# controller.net
KiCad netlist of a schematic drawn in EAGLE
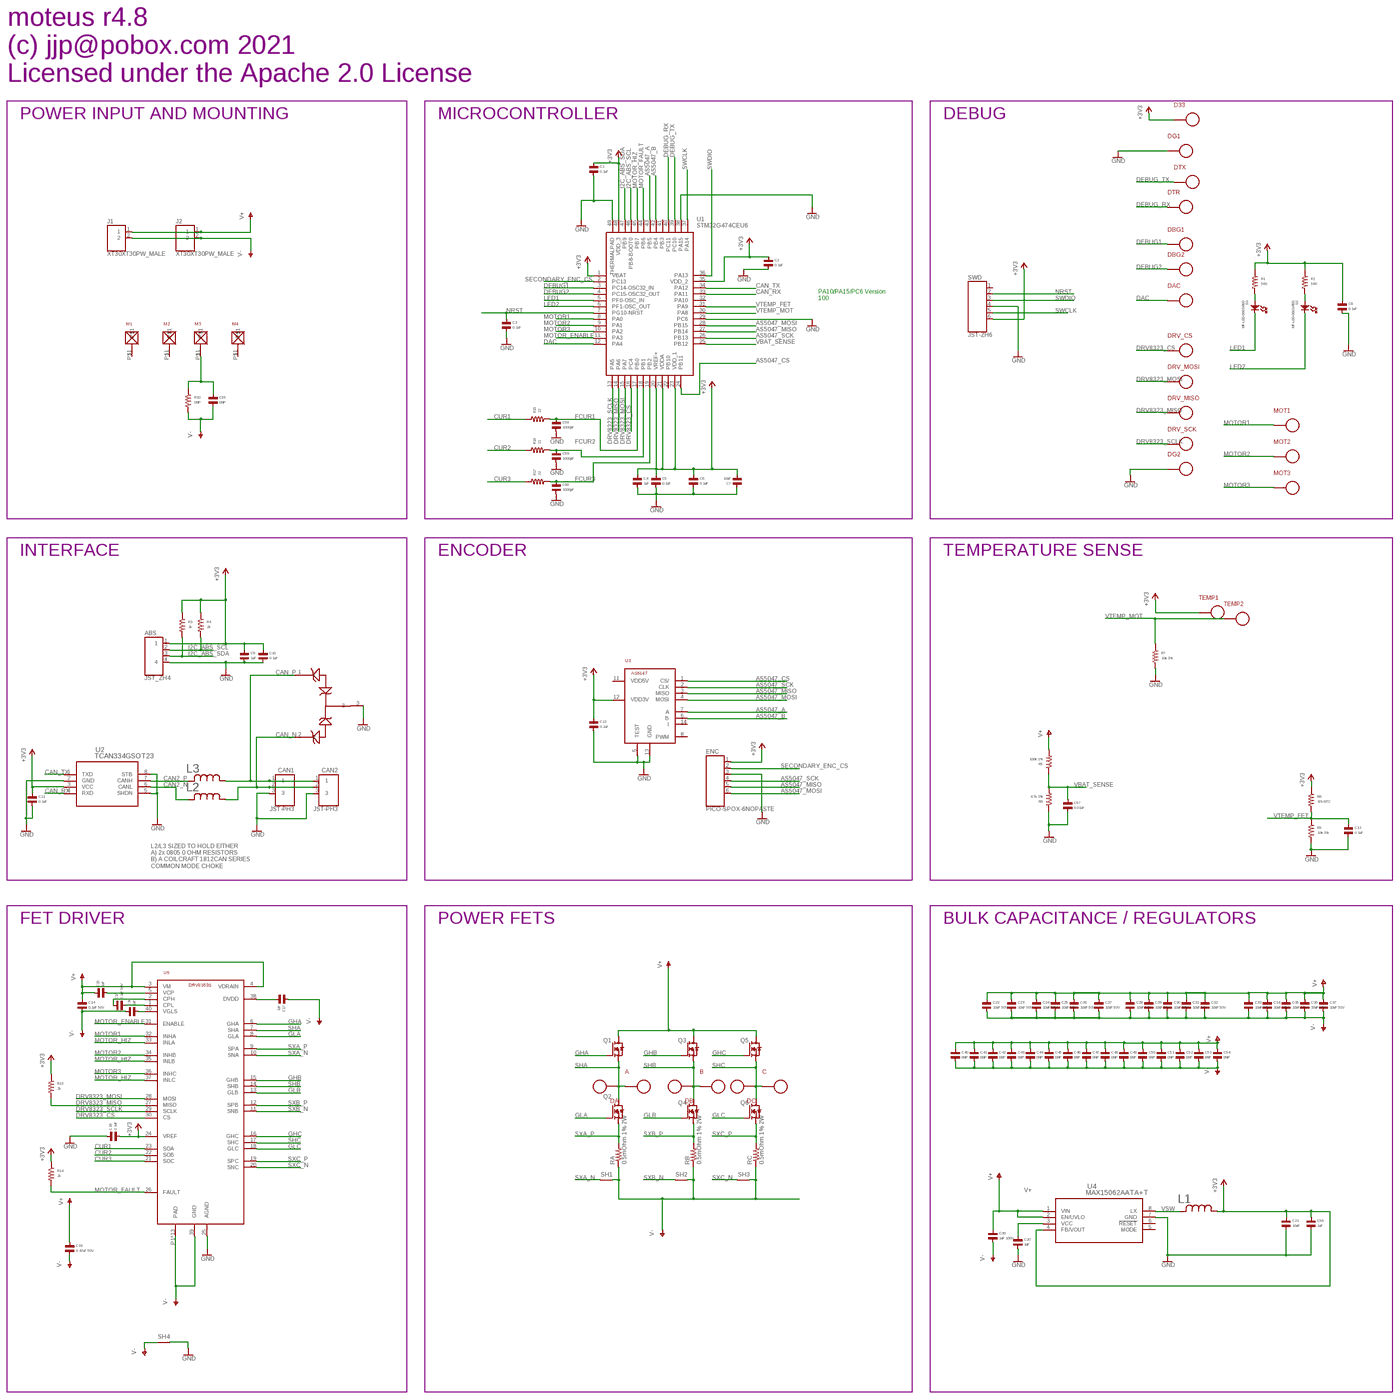
[diagram p0: schematic, sheet 1, overview]
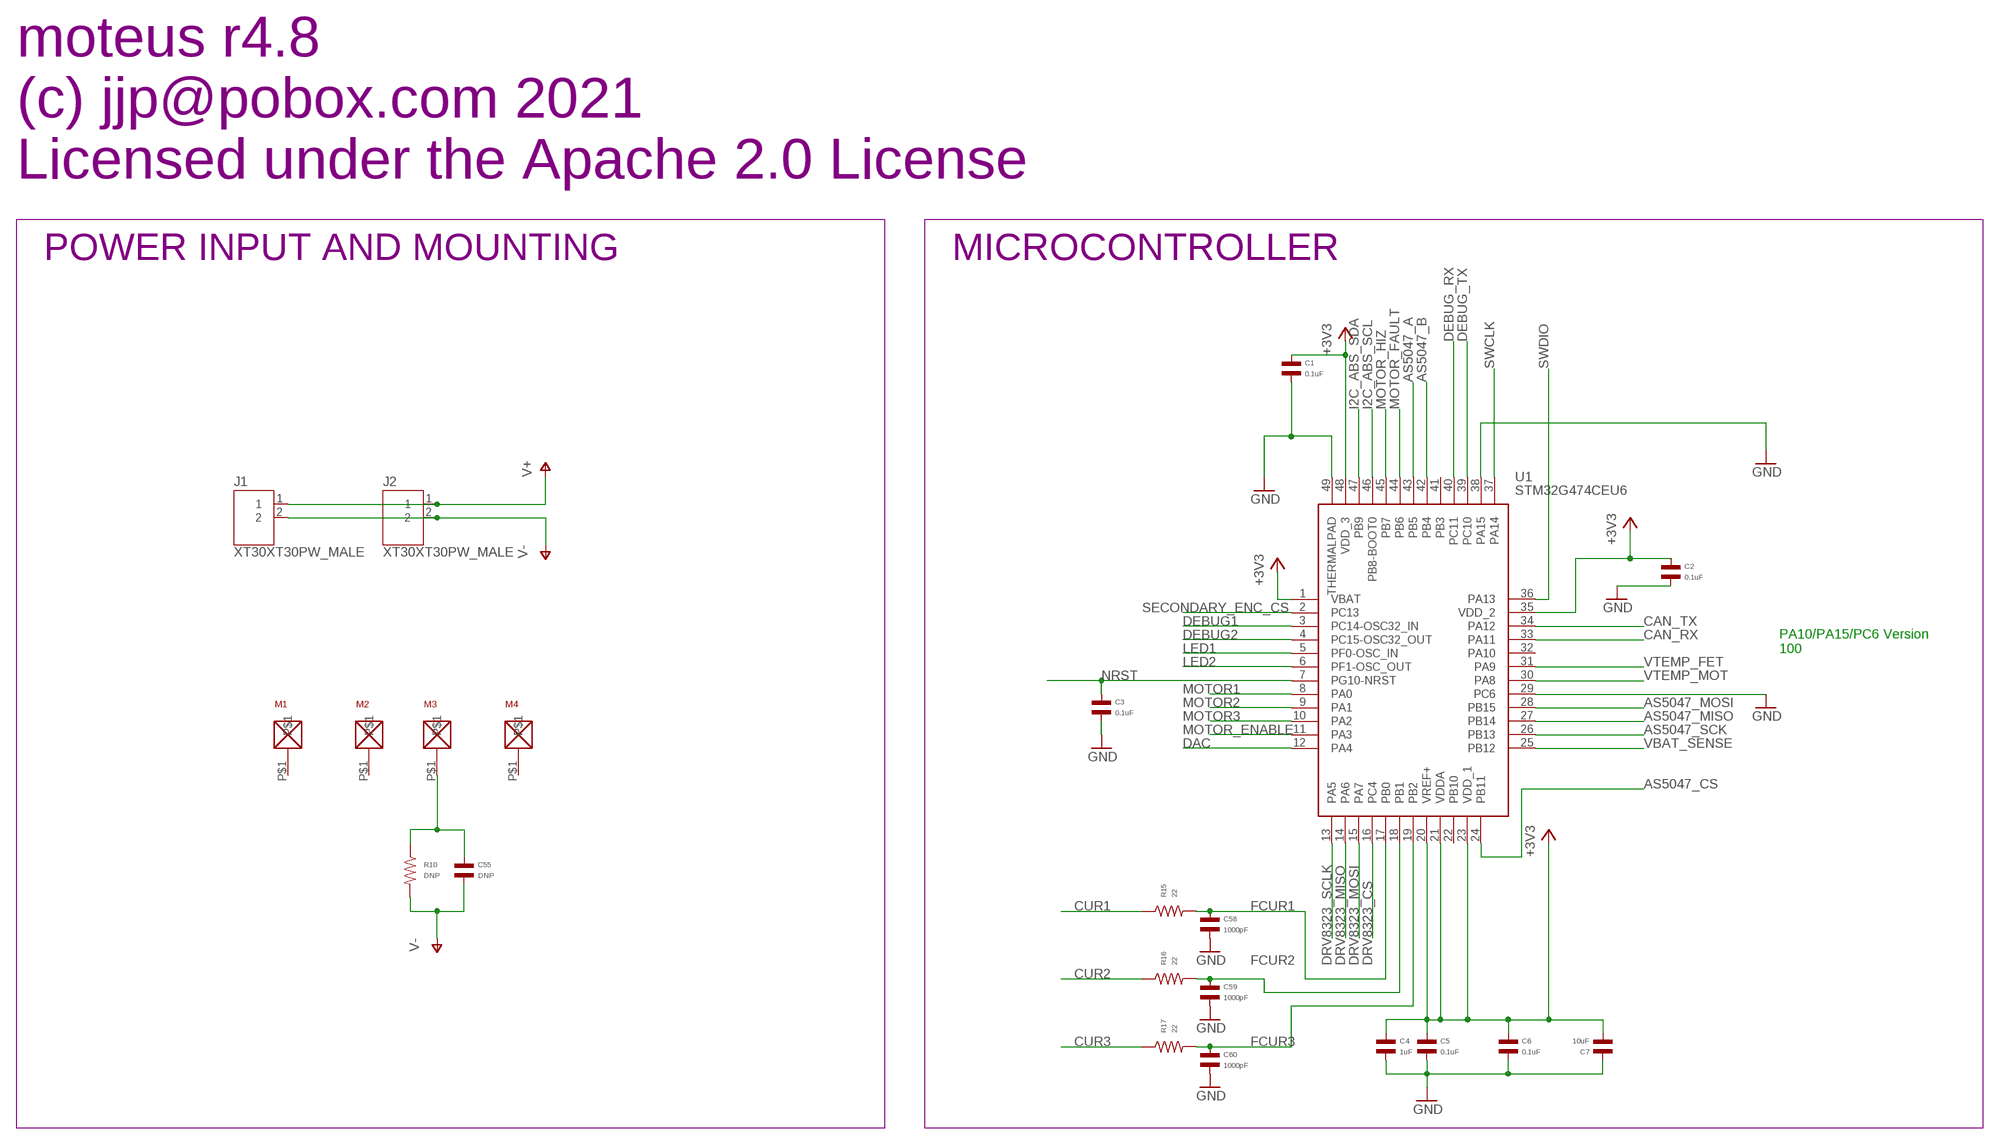
[diagram p1: schematic, sheet 1, part 1 of 4]
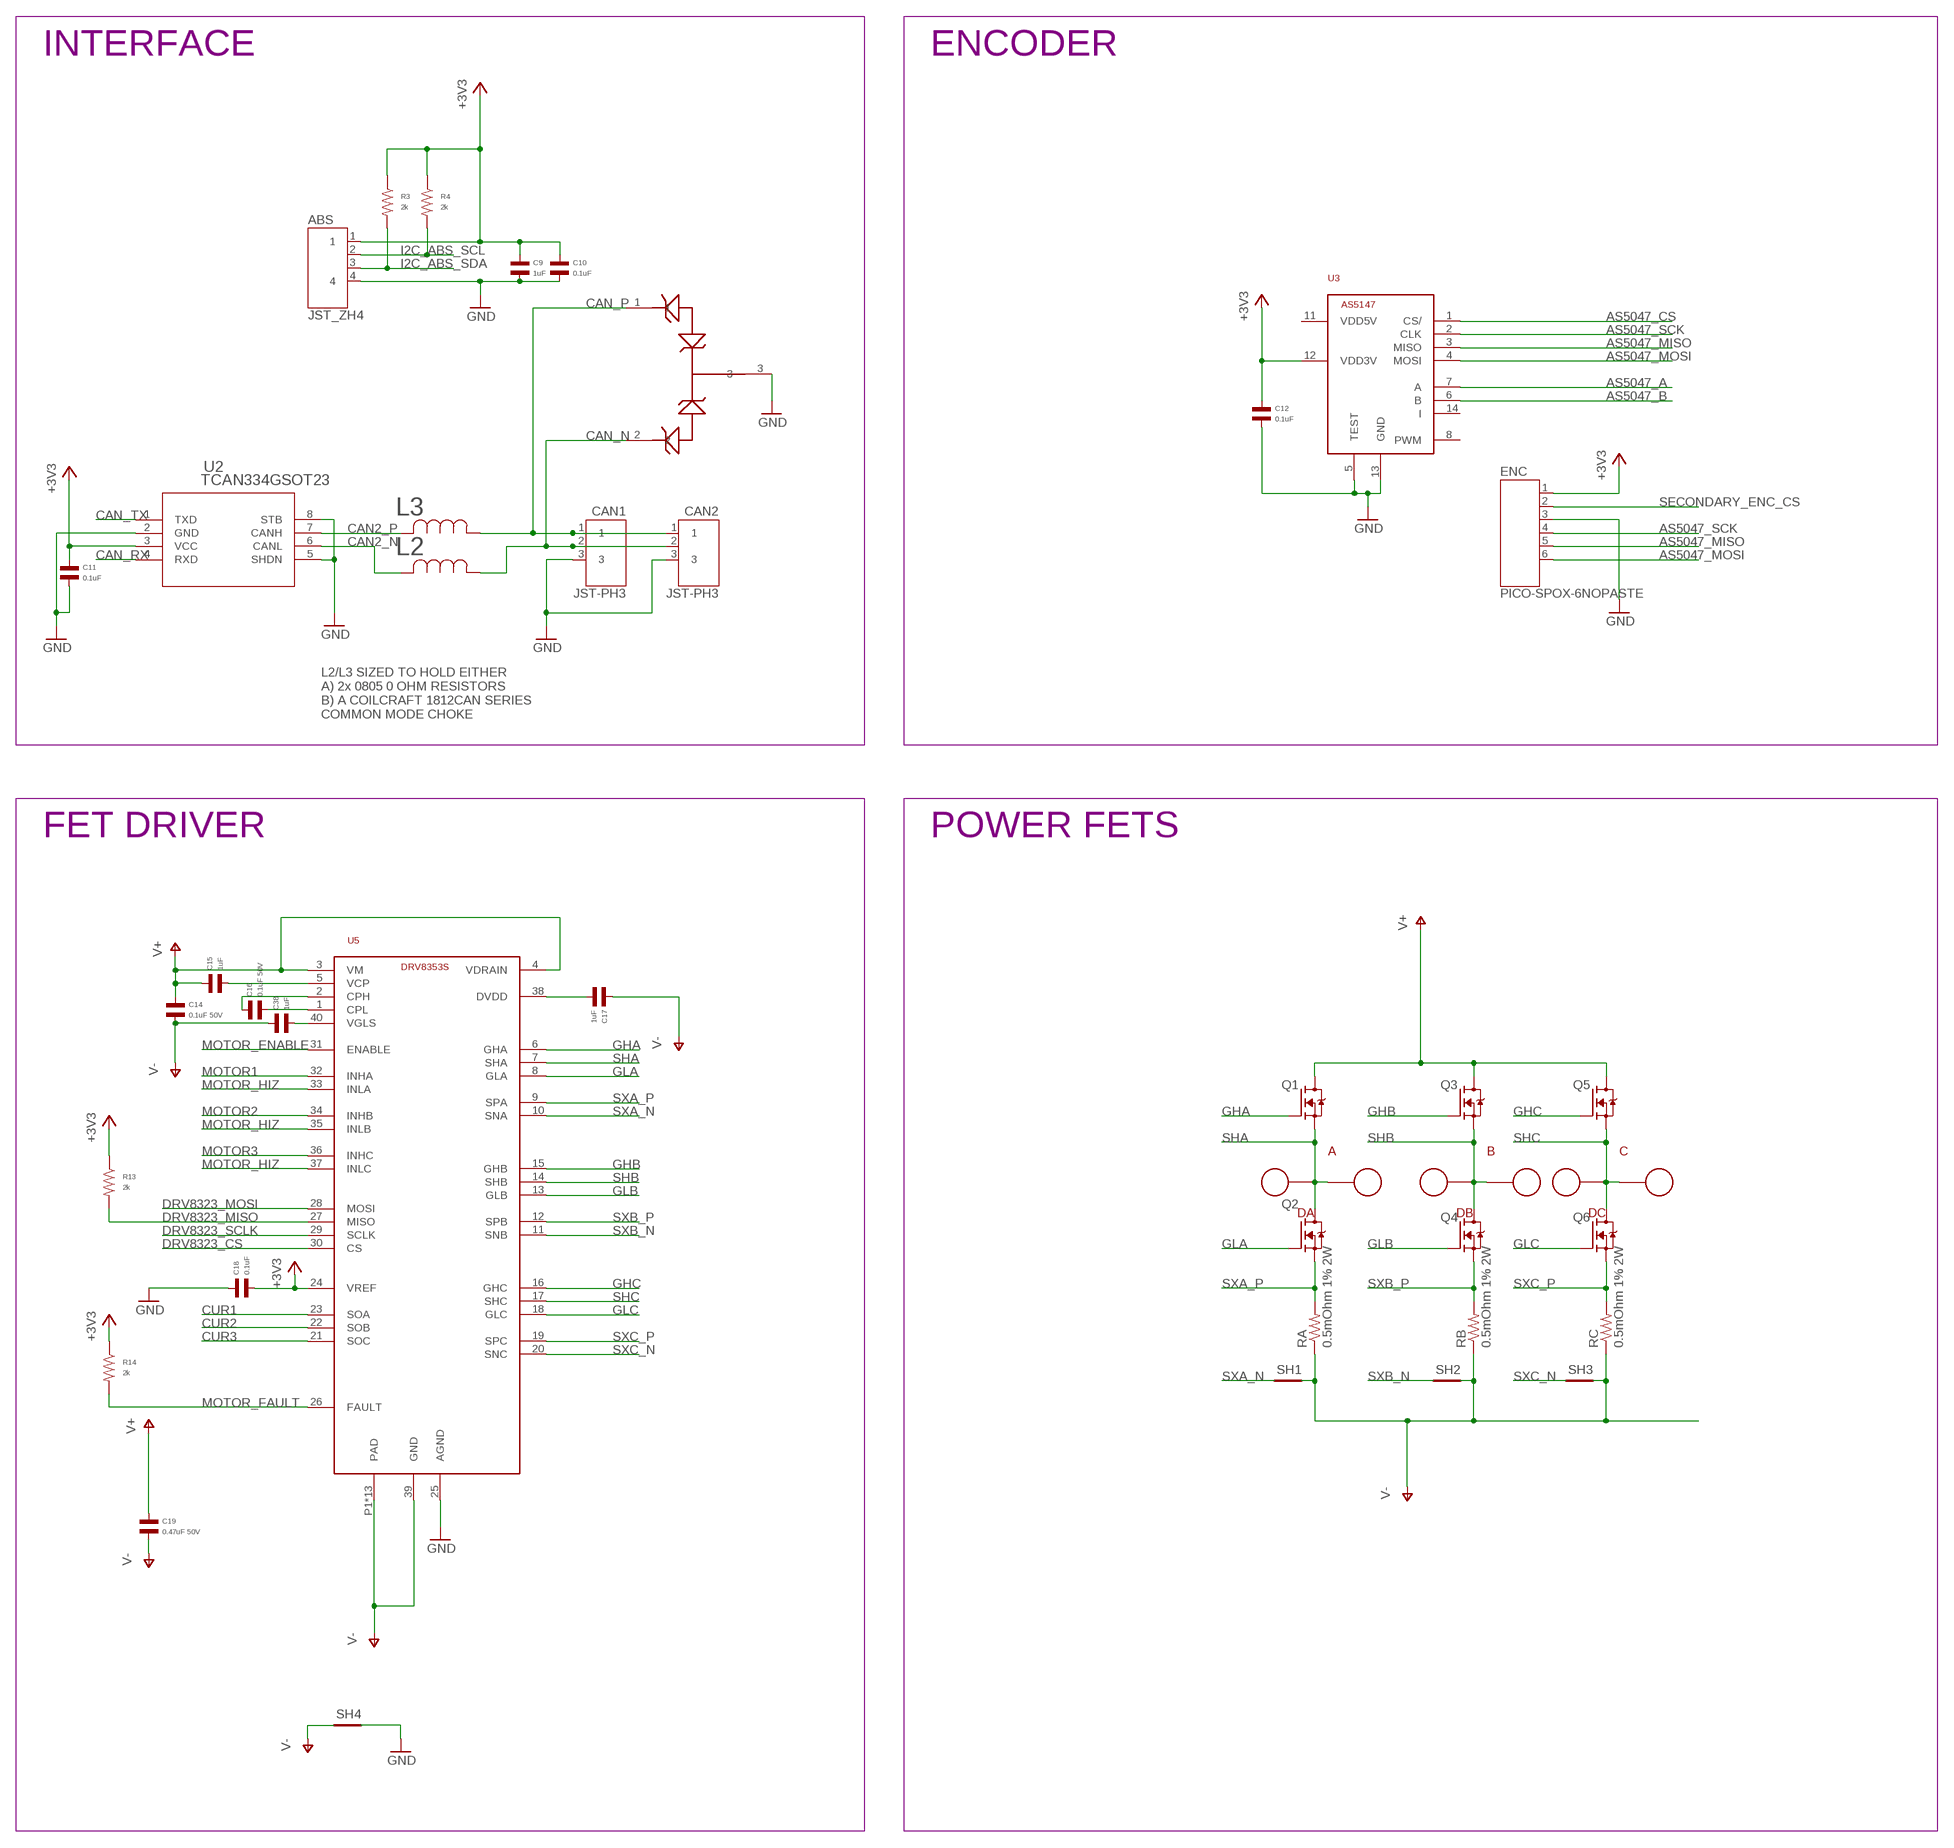
[diagram p2: schematic, sheet 1, part 2 of 4]
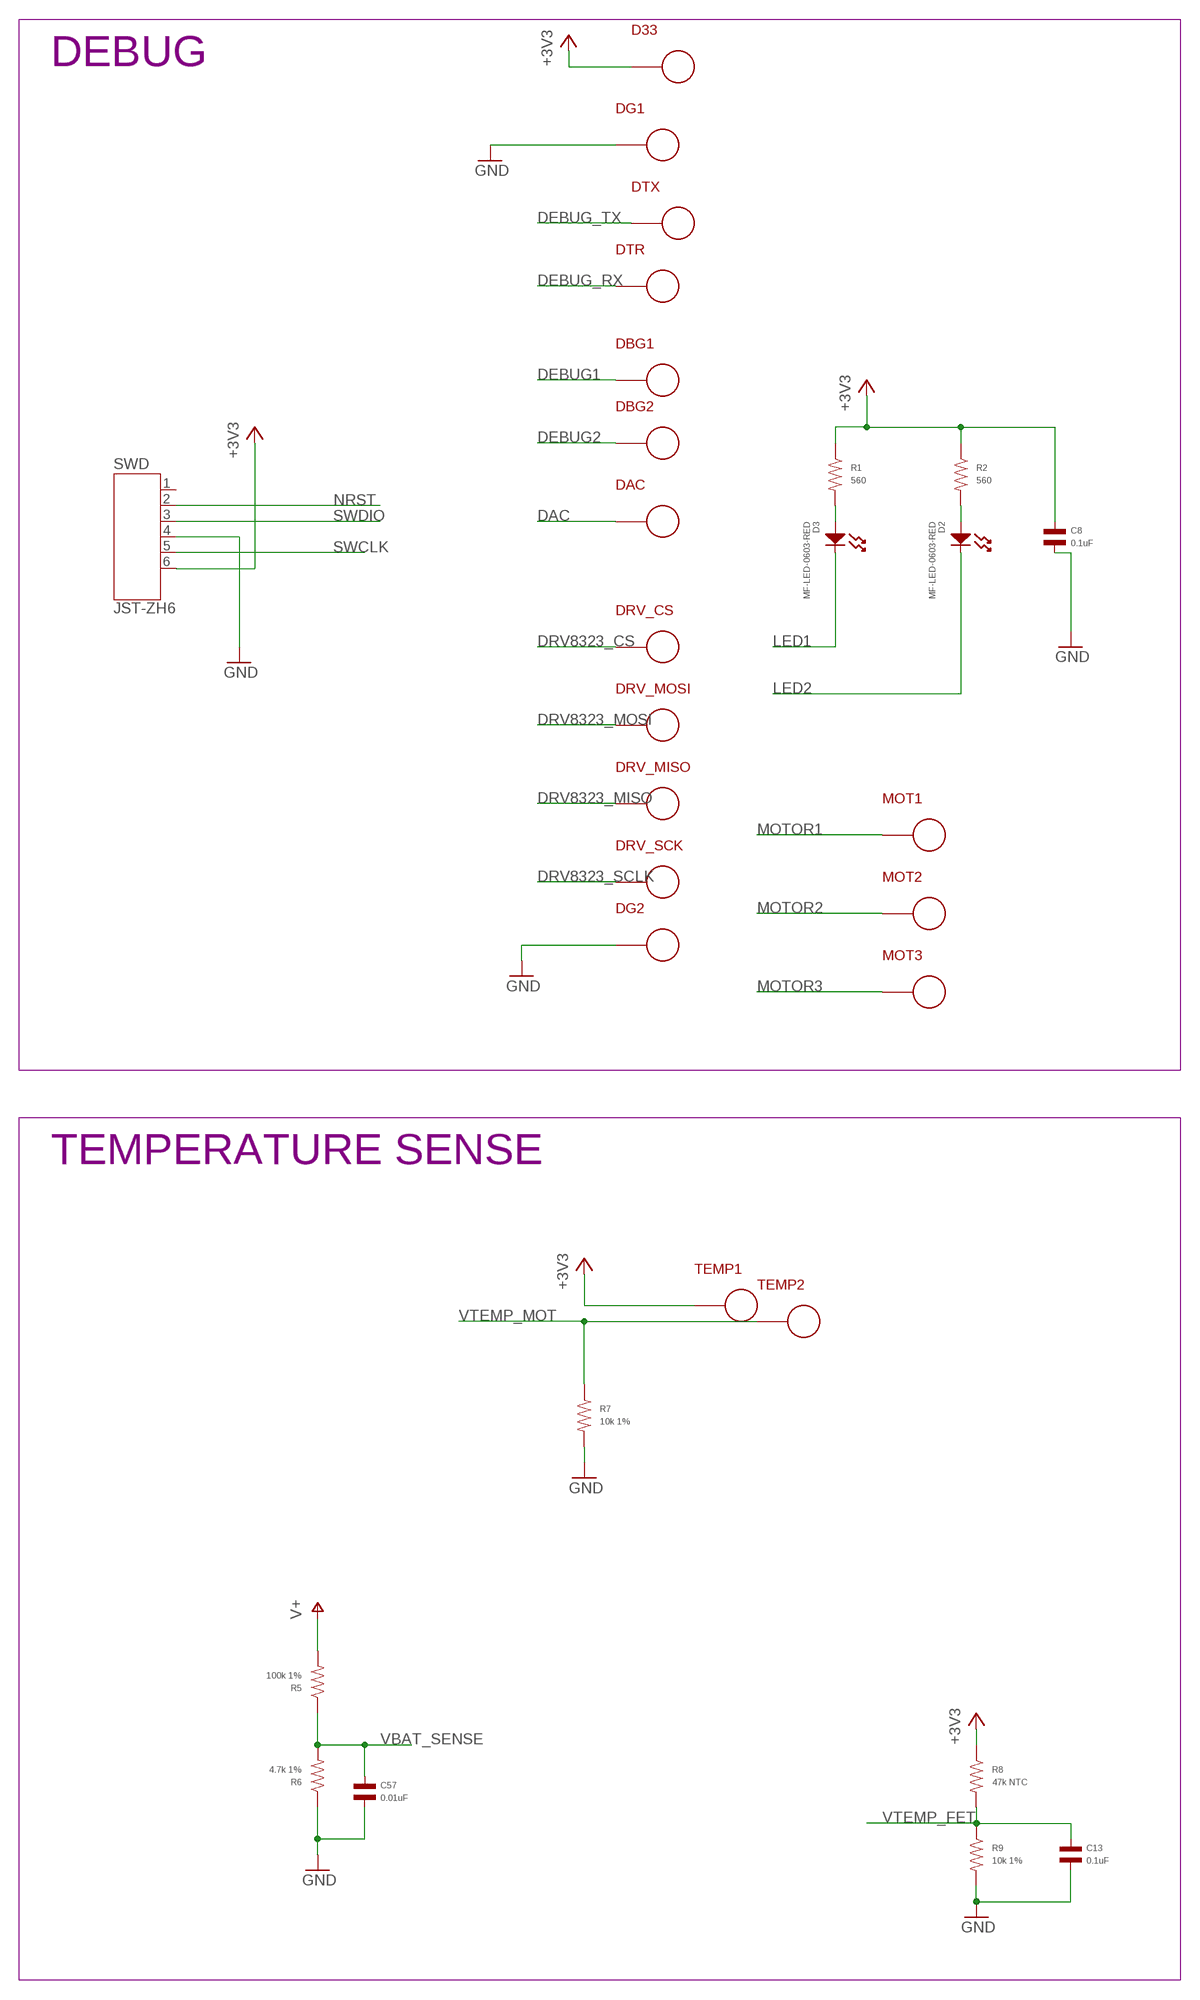
[diagram p3: schematic, sheet 1, part 3 of 4]
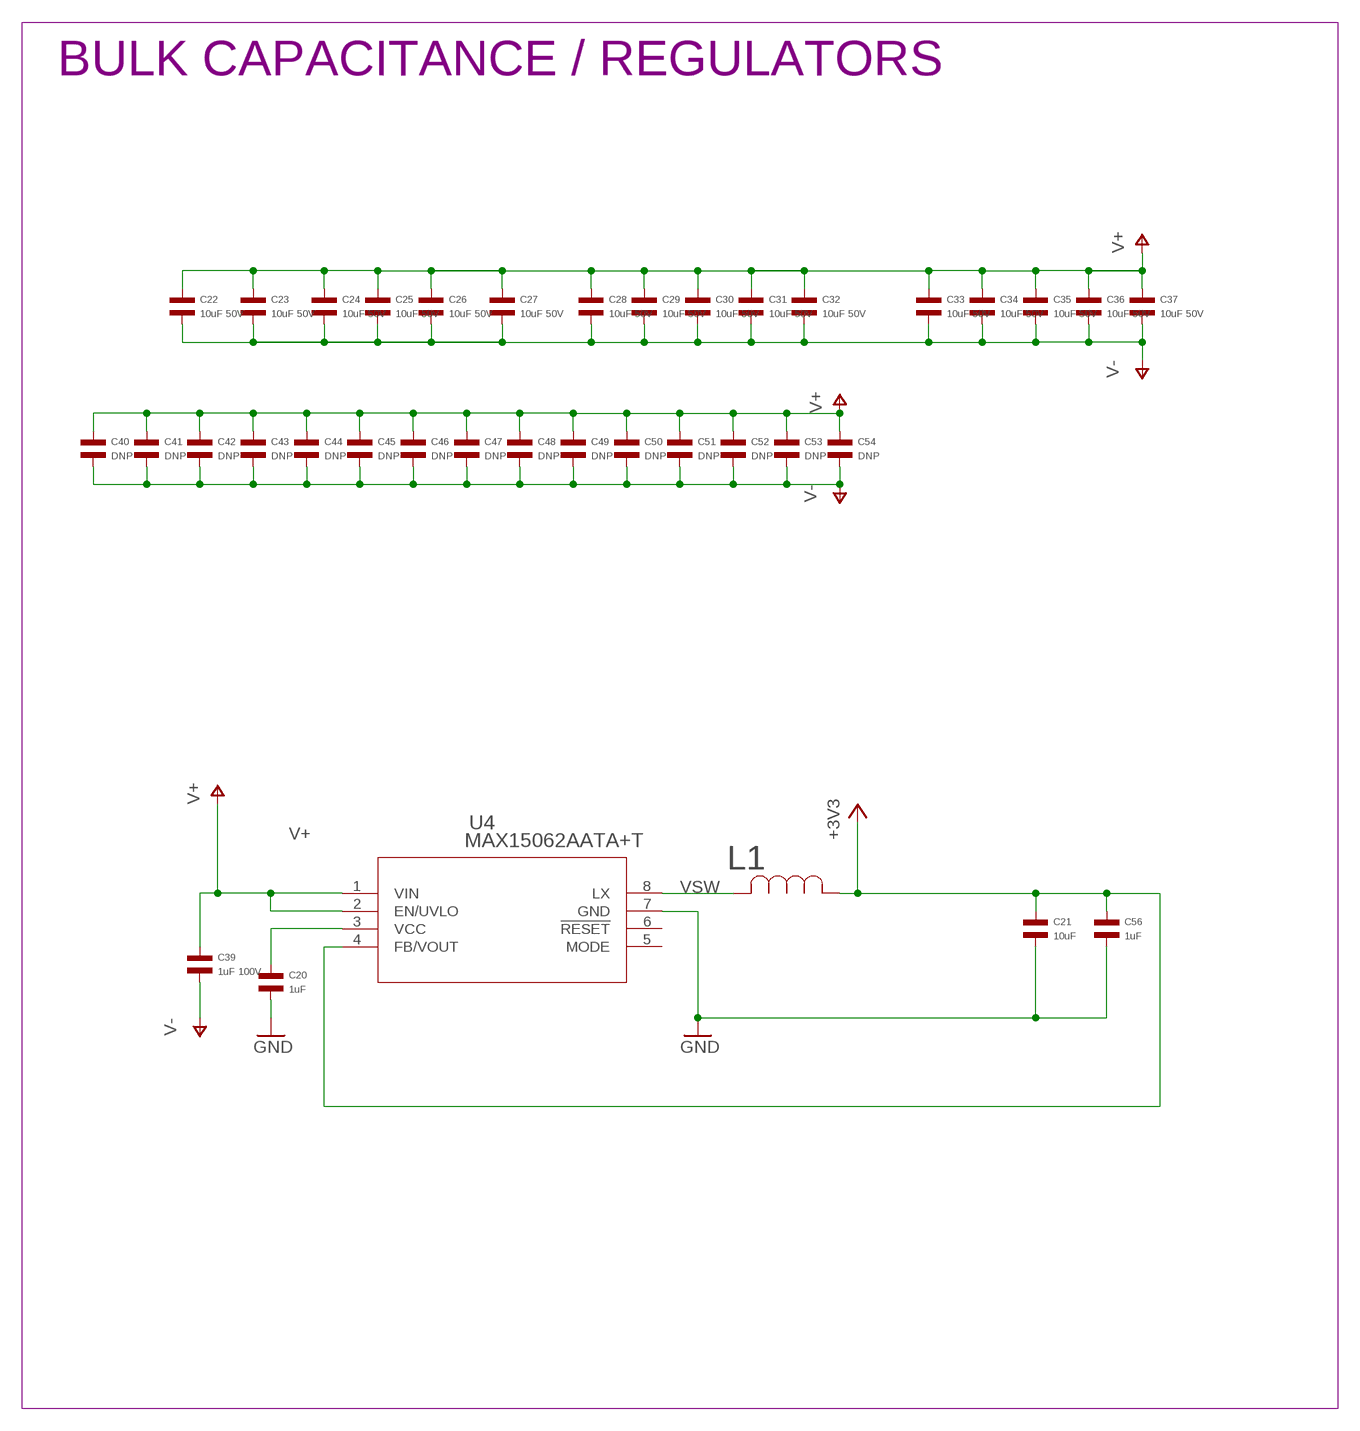
[diagram p4: schematic, sheet 1, part 4 of 4]

(export (version "E")
  (design (tool "Eeschema 10.0.6"))
  (components
    (comp (ref "A")
      (value "PAD16AWG_PAD")
      (footprint "eagle-import:16AWG_PAD")
      (libsource (lib "eagle-import") (part "PAD16AWG_PAD"))
    )
    (comp (ref "ABS")
      (value "JST_ZH4")
      (footprint "eagle-import:JST_S4B-ZR-SM4A-TF(LF)(SN)")
      (fields (field (name "MF") "JST") (field (name "MPN") "S4B-ZR-SM4A-TF(LF)(SN)"))
      (libsource (lib "eagle-import") (part "JST_ZH4"))
    )
    (comp (ref "B")
      (value "PAD16AWG_PAD")
      (footprint "eagle-import:16AWG_PAD")
      (libsource (lib "eagle-import") (part "PAD16AWG_PAD"))
    )
    (comp (ref "C")
      (value "PAD16AWG_PAD")
      (footprint "eagle-import:16AWG_PAD")
      (libsource (lib "eagle-import") (part "PAD16AWG_PAD"))
    )
    (comp (ref "C1")
      (value "0.1uF")
      (footprint "eagle-import:C0402")
      (fields (field (name "HOUSEPART") "YES") (field (name "MPN") "MF-CAP-0402-0.1uF"))
      (libsource (lib "eagle-import") (part "mfpassives_CAPACITOR_NP_0402"))
    )
    (comp (ref "C2")
      (value "0.1uF")
      (footprint "eagle-import:C0402")
      (fields (field (name "HOUSEPART") "YES") (field (name "MPN") "MF-CAP-0402-0.1uF"))
      (libsource (lib "eagle-import") (part "mfpassives_CAPACITOR_NP_0402"))
    )
    (comp (ref "C3")
      (value "0.1uF")
      (footprint "eagle-import:C0402")
      (fields (field (name "HOUSEPART") "YES") (field (name "MPN") "MF-CAP-0402-0.1uF"))
      (libsource (lib "eagle-import") (part "mfpassives_CAPACITOR_NP_0402"))
    )
    (comp (ref "C4")
      (value "1uF")
      (footprint "eagle-import:C0402")
      (fields (field (name "HOUSEPART") "YES") (field (name "MPN") "MF-CAP-0402-1uF"))
      (libsource (lib "eagle-import") (part "mfpassives_CAPACITOR_NP_0402"))
    )
    (comp (ref "C5")
      (value "0.1uF")
      (footprint "eagle-import:C0402")
      (fields (field (name "HOUSEPART") "YES") (field (name "MPN") "MF-CAP-0402-0.1uF"))
      (libsource (lib "eagle-import") (part "mfpassives_CAPACITOR_NP_0402"))
    )
    (comp (ref "C6")
      (value "0.1uF")
      (footprint "eagle-import:C0402")
      (fields (field (name "HOUSEPART") "YES") (field (name "MPN") "MF-CAP-0402-0.1uF"))
      (libsource (lib "eagle-import") (part "mfpassives_CAPACITOR_NP_0402"))
    )
    (comp (ref "C7")
      (value "10uF")
      (footprint "eagle-import:C1206")
      (fields (field (name "HOUSEPART") "YES") (field (name "MPN") "MF-CAP-1206-10uF"))
      (libsource (lib "eagle-import") (part "mfpassives_CAPACITOR_NP_1206"))
    )
    (comp (ref "C8")
      (value "0.1uF")
      (footprint "eagle-import:C0402")
      (fields (field (name "HOUSEPART") "YES") (field (name "MPN") "MF-CAP-0402-0.1uF"))
      (libsource (lib "eagle-import") (part "mfpassives_CAPACITOR_NP_0402"))
    )
    (comp (ref "C9")
      (value "1uF")
      (footprint "eagle-import:C0402")
      (fields (field (name "HOUSEPART") "YES") (field (name "MPN") "MF-CAP-0402-1uF"))
      (libsource (lib "eagle-import") (part "mfpassives_CAPACITOR_NP_0402"))
    )
    (comp (ref "C10")
      (value "0.1uF")
      (footprint "eagle-import:C0402")
      (fields (field (name "HOUSEPART") "YES") (field (name "MPN") "MF-CAP-0402-0.1uF"))
      (libsource (lib "eagle-import") (part "mfpassives_CAPACITOR_NP_0402"))
    )
    (comp (ref "C11")
      (value "0.1uF")
      (footprint "eagle-import:C0402")
      (fields (field (name "HOUSEPART") "YES") (field (name "MPN") "MF-CAP-0402-0.1uF"))
      (libsource (lib "eagle-import") (part "mfpassives_CAPACITOR_NP_0402"))
    )
    (comp (ref "C12")
      (value "0.1uF")
      (footprint "eagle-import:C0402")
      (fields (field (name "HOUSEPART") "YES") (field (name "MPN") "MF-CAP-0402-0.1uF"))
      (libsource (lib "eagle-import") (part "mfpassives_CAPACITOR_NP_0402"))
    )
    (comp (ref "C13")
      (value "0.1uF")
      (footprint "eagle-import:C0402")
      (fields (field (name "HOUSEPART") "YES") (field (name "MPN") "MF-CAP-0402-0.1uF"))
      (libsource (lib "eagle-import") (part "mfpassives_CAPACITOR_NP_0402"))
    )
    (comp (ref "C14")
      (value "0.1uF 50V")
      (footprint "eagle-import:C0402")
      (fields (field (name "MF") "TDK") (field (name "MPN") "CGA2B3X7R1H104K050BB"))
      (libsource (lib "eagle-import") (part "mfpassives_CAPACITOR_NP_0402"))
    )
    (comp (ref "C15")
      (value "1uF")
      (footprint "eagle-import:C0402")
      (fields (field (name "HOUSEPART") "YES") (field (name "MPN") "MF-CAP-0402-1uF"))
      (libsource (lib "eagle-import") (part "mfpassives_CAPACITOR_NP_0402"))
    )
    (comp (ref "C16")
      (value "0.1uF 50V")
      (footprint "eagle-import:C0402")
      (fields (field (name "MF") "TDK") (field (name "MPN") "CGA2B3X7R1H104K050BB"))
      (libsource (lib "eagle-import") (part "mfpassives_CAPACITOR_NP_0402"))
    )
    (comp (ref "C17")
      (value "1uF")
      (footprint "eagle-import:C0402")
      (fields (field (name "HOUSEPART") "YES") (field (name "MPN") "MF-CAP-0402-1uF"))
      (libsource (lib "eagle-import") (part "mfpassives_CAPACITOR_NP_0402"))
    )
    (comp (ref "C18")
      (value "0.1uF")
      (footprint "eagle-import:C0402")
      (fields (field (name "HOUSEPART") "YES") (field (name "MPN") "MF-CAP-0402-0.1uF"))
      (libsource (lib "eagle-import") (part "mfpassives_CAPACITOR_NP_0402"))
    )
    (comp (ref "C19")
      (value "0.47uF 50V")
      (footprint "eagle-import:C0402")
      (fields (field (name "MF") "Murata") (field (name "MPN") "GRM155R61H474KE11D"))
      (libsource (lib "eagle-import") (part "mfpassives_CAPACITOR_NP_0402"))
    )
    (comp (ref "C20")
      (value "1uF")
      (footprint "eagle-import:C0603")
      (fields (field (name "HOUSEPART") "1") (field (name "MPN") "MF-CAP-0603-1uF"))
      (libsource (lib "eagle-import") (part "mfpassives_CAPACITOR_NP_0603"))
    )
    (comp (ref "C21")
      (value "10uF")
      (footprint "eagle-import:C1206")
      (fields (field (name "HOUSEPART") "1") (field (name "MPN") "MF-CAP-1206-10uF"))
      (libsource (lib "eagle-import") (part "mfpassives_CAPACITOR_NP_1206"))
    )
    (comp (ref "C22")
      (value "10uF 50V")
      (footprint "eagle-import:C1206")
      (fields (field (name "MF") "TDK") (field (name "MPN") "C3216X7R1H106K160AE"))
      (libsource (lib "eagle-import") (part "mfpassives_CAPACITOR_NP_1206"))
    )
    (comp (ref "C23")
      (value "10uF 50V")
      (footprint "eagle-import:C1206")
      (fields (field (name "MF") "TDK") (field (name "MPN") "C3216X7R1H106K160AE"))
      (libsource (lib "eagle-import") (part "mfpassives_CAPACITOR_NP_1206"))
    )
    (comp (ref "C24")
      (value "10uF 50V")
      (footprint "eagle-import:C1206")
      (fields (field (name "MF") "TDK") (field (name "MPN") "C3216X7R1H106K160AE"))
      (libsource (lib "eagle-import") (part "mfpassives_CAPACITOR_NP_1206"))
    )
    (comp (ref "C25")
      (value "10uF 50V")
      (footprint "eagle-import:C1206")
      (fields (field (name "MF") "TDK") (field (name "MPN") "C3216X7R1H106K160AE"))
      (libsource (lib "eagle-import") (part "mfpassives_CAPACITOR_NP_1206"))
    )
    (comp (ref "C26")
      (value "10uF 50V")
      (footprint "eagle-import:C1206")
      (fields (field (name "MF") "TDK") (field (name "MPN") "C3216X7R1H106K160AE"))
      (libsource (lib "eagle-import") (part "mfpassives_CAPACITOR_NP_1206"))
    )
    (comp (ref "C27")
      (value "10uF 50V")
      (footprint "eagle-import:C1206")
      (fields (field (name "MF") "TDK") (field (name "MPN") "C3216X7R1H106K160AE"))
      (libsource (lib "eagle-import") (part "mfpassives_CAPACITOR_NP_1206"))
    )
    (comp (ref "C28")
      (value "10uF 50V")
      (footprint "eagle-import:C1206")
      (fields (field (name "MF") "TDK") (field (name "MPN") "C3216X7R1H106K160AE"))
      (libsource (lib "eagle-import") (part "mfpassives_CAPACITOR_NP_1206"))
    )
    (comp (ref "C29")
      (value "10uF 50V")
      (footprint "eagle-import:C1206")
      (fields (field (name "MF") "TDK") (field (name "MPN") "C3216X7R1H106K160AE"))
      (libsource (lib "eagle-import") (part "mfpassives_CAPACITOR_NP_1206"))
    )
    (comp (ref "C30")
      (value "10uF 50V")
      (footprint "eagle-import:C1206")
      (fields (field (name "MF") "TDK") (field (name "MPN") "C3216X7R1H106K160AE"))
      (libsource (lib "eagle-import") (part "mfpassives_CAPACITOR_NP_1206"))
    )
    (comp (ref "C31")
      (value "10uF 50V")
      (footprint "eagle-import:C1206")
      (fields (field (name "MF") "TDK") (field (name "MPN") "C3216X7R1H106K160AE"))
      (libsource (lib "eagle-import") (part "mfpassives_CAPACITOR_NP_1206"))
    )
    (comp (ref "C32")
      (value "10uF 50V")
      (footprint "eagle-import:C1206")
      (fields (field (name "MF") "TDK") (field (name "MPN") "C3216X7R1H106K160AE"))
      (libsource (lib "eagle-import") (part "mfpassives_CAPACITOR_NP_1206"))
    )
    (comp (ref "C33")
      (value "10uF 50V")
      (footprint "eagle-import:C1206")
      (fields (field (name "MF") "TDK") (field (name "MPN") "C3216X7R1H106K160AE"))
      (libsource (lib "eagle-import") (part "mfpassives_CAPACITOR_NP_1206"))
    )
    (comp (ref "C34")
      (value "10uF 50V")
      (footprint "eagle-import:C1206")
      (fields (field (name "MF") "TDK") (field (name "MPN") "C3216X7R1H106K160AE"))
      (libsource (lib "eagle-import") (part "mfpassives_CAPACITOR_NP_1206"))
    )
    (comp (ref "C35")
      (value "10uF 50V")
      (footprint "eagle-import:C1206_NOBORDER")
      (fields (field (name "MF") "TDK") (field (name "MPN") "C3216X7R1H106K160AE"))
      (libsource (lib "eagle-import") (part "CAPACITOR_NP_1206_NOBORDER"))
    )
    (comp (ref "C36")
      (value "10uF 50V")
      (footprint "eagle-import:C1206")
      (fields (field (name "MF") "TDK") (field (name "MPN") "C3216X7R1H106K160AE"))
      (libsource (lib "eagle-import") (part "mfpassives_CAPACITOR_NP_1206"))
    )
    (comp (ref "C37")
      (value "10uF 50V")
      (footprint "eagle-import:C1206")
      (fields (field (name "MF") "TDK") (field (name "MPN") "C3216X7R1H106K160AE"))
      (libsource (lib "eagle-import") (part "mfpassives_CAPACITOR_NP_1206"))
    )
    (comp (ref "C38")
      (value "1uF")
      (footprint "eagle-import:C0402")
      (fields (field (name "HOUSEPART") "YES") (field (name "MPN") "MF-CAP-0402-1uF"))
      (libsource (lib "eagle-import") (part "mfpassives_CAPACITOR_NP_0402"))
    )
    (comp (ref "C39")
      (value "1uF 100V")
      (footprint "eagle-import:C0805")
      (fields (field (name "MF") "MURATA") (field (name "MPN") "GCM21BC72A105KE36L"))
      (libsource (lib "eagle-import") (part "mfpassives_CAPACITOR_NP_0805"))
    )
    (comp (ref "C40")
      (value "DNP")
      (footprint "eagle-import:C1206_NOCREAM")
      (libsource (lib "eagle-import") (part "CAPACITOR_NP_1206_NOCREAM"))
    )
    (comp (ref "C41")
      (value "DNP")
      (footprint "eagle-import:C1206_NOCREAM")
      (libsource (lib "eagle-import") (part "CAPACITOR_NP_1206_NOCREAM"))
    )
    (comp (ref "C42")
      (value "DNP")
      (footprint "eagle-import:C1206_NOCREAM")
      (libsource (lib "eagle-import") (part "CAPACITOR_NP_1206_NOCREAM"))
    )
    (comp (ref "C43")
      (value "DNP")
      (footprint "eagle-import:C1206_NOCREAM")
      (libsource (lib "eagle-import") (part "CAPACITOR_NP_1206_NOCREAM"))
    )
    (comp (ref "C44")
      (value "DNP")
      (footprint "eagle-import:C1206_NOCREAM")
      (libsource (lib "eagle-import") (part "CAPACITOR_NP_1206_NOCREAM"))
    )
    (comp (ref "C45")
      (value "DNP")
      (footprint "eagle-import:C1206_NOCREAM")
      (libsource (lib "eagle-import") (part "CAPACITOR_NP_1206_NOCREAM"))
    )
    (comp (ref "C46")
      (value "DNP")
      (footprint "eagle-import:C1206_NOCREAM")
      (libsource (lib "eagle-import") (part "CAPACITOR_NP_1206_NOCREAM"))
    )
    (comp (ref "C47")
      (value "DNP")
      (footprint "eagle-import:C1206_NOCREAM")
      (libsource (lib "eagle-import") (part "CAPACITOR_NP_1206_NOCREAM"))
    )
    (comp (ref "C48")
      (value "DNP")
      (footprint "eagle-import:C1206_NOCREAM")
      (libsource (lib "eagle-import") (part "CAPACITOR_NP_1206_NOCREAM"))
    )
    (comp (ref "C49")
      (value "DNP")
      (footprint "eagle-import:C1206_NOCREAM")
      (libsource (lib "eagle-import") (part "CAPACITOR_NP_1206_NOCREAM"))
    )
    (comp (ref "C50")
      (value "DNP")
      (footprint "eagle-import:C1206_NOCREAM")
      (libsource (lib "eagle-import") (part "CAPACITOR_NP_1206_NOCREAM"))
    )
    (comp (ref "C51")
      (value "DNP")
      (footprint "eagle-import:C1206_NOCREAM")
      (libsource (lib "eagle-import") (part "CAPACITOR_NP_1206_NOCREAM"))
    )
    (comp (ref "C52")
      (value "DNP")
      (footprint "eagle-import:C1206_NOCREAM")
      (libsource (lib "eagle-import") (part "CAPACITOR_NP_1206_NOCREAM"))
    )
    (comp (ref "C53")
      (value "DNP")
      (footprint "eagle-import:C1206_NOCREAM")
      (libsource (lib "eagle-import") (part "CAPACITOR_NP_1206_NOCREAM"))
    )
    (comp (ref "C54")
      (value "DNP")
      (footprint "eagle-import:C1206_NOCREAM")
      (libsource (lib "eagle-import") (part "CAPACITOR_NP_1206_NOCREAM"))
    )
    (comp (ref "C55")
      (value "DNP")
      (footprint "eagle-import:C0402")
      (fields (field (name "POPULATE") "0"))
      (libsource (lib "eagle-import") (part "mfpassives_CAPACITOR_NP_0402"))
    )
    (comp (ref "C56")
      (value "1uF")
      (footprint "eagle-import:C0402")
      (fields (field (name "HOUSEPART") "YES") (field (name "MPN") "MF-CAP-0402-1uF"))
      (libsource (lib "eagle-import") (part "mfpassives_CAPACITOR_NP_0402"))
    )
    (comp (ref "C57")
      (value "0.01uF")
      (footprint "eagle-import:C0402")
      (fields (field (name "HOUSEPART") "YES") (field (name "MPN") "MF-CAP-0402-0.01uF"))
      (libsource (lib "eagle-import") (part "mfpassives_CAPACITOR_NP_0402"))
    )
    (comp (ref "C58")
      (value "1000pF")
      (footprint "eagle-import:C0402")
      (fields (field (name "HOUSEPART") "1") (field (name "MPN") "MF-CAP-0402-1nF"))
      (libsource (lib "eagle-import") (part "mfpassives_CAPACITOR_NP_0402"))
    )
    (comp (ref "C59")
      (value "1000pF")
      (footprint "eagle-import:C0402")
      (fields (field (name "HOUSEPART") "1") (field (name "MPN") "MF-CAP-0402-1nF"))
      (libsource (lib "eagle-import") (part "mfpassives_CAPACITOR_NP_0402"))
    )
    (comp (ref "C60")
      (value "1000pF")
      (footprint "eagle-import:C0402")
      (fields (field (name "HOUSEPART") "1") (field (name "MPN") "MF-CAP-0402-1nF"))
      (libsource (lib "eagle-import") (part "mfpassives_CAPACITOR_NP_0402"))
    )
    (comp (ref "CAN1")
      (value "JST-PH3")
      (footprint "eagle-import:JST_S3B-PH-SM4-TB(LF)(SN)")
      (fields (field (name "MF") "JST") (field (name "MPN") "S3B-PH-SM4-TB(LF)(SN)"))
      (libsource (lib "eagle-import") (part "JST-PH3"))
    )
    (comp (ref "CAN2")
      (value "JST-PH3")
      (footprint "eagle-import:JST_S3B-PH-SM4-TB(LF)(SN)")
      (fields (field (name "MF") "JST") (field (name "MPN") "S3B-PH-SM4-TB(LF)(SN)"))
      (libsource (lib "eagle-import") (part "JST-PH3"))
    )
    (comp (ref "D2")
      (value "MF-LED-0603-RED")
      (footprint "eagle-import:LED0603")
      (fields (field (name "HOUSEPART") "YES") (field (name "MPN") "MF-LED-0603-GREEN"))
      (libsource (lib "eagle-import") (part "LED_SINGLE-0603-RED"))
    )
    (comp (ref "D3")
      (value "MF-LED-0603-RED")
      (footprint "eagle-import:LED0603")
      (fields (field (name "HOUSEPART") "YES"))
      (libsource (lib "eagle-import") (part "LED_SINGLE-0603-RED"))
    )
    (comp (ref "D4")
      (value "DUAL_TVS")
      (footprint "eagle-import:SOT23-3")
      (fields (field (name "MPN") "CDSOT23-0502B"))
      (libsource (lib "eagle-import") (part "DUAL_TVS"))
    )
    (comp (ref "D33")
      (value "PAD24AWG_PAD")
      (footprint "eagle-import:24AWG_PAD")
      (libsource (lib "eagle-import") (part "PAD24AWG_PAD"))
    )
    (comp (ref "DA")
      (value "PAD24AWG_PAD")
      (footprint "eagle-import:24AWG_PAD")
      (libsource (lib "eagle-import") (part "PAD24AWG_PAD"))
    )
    (comp (ref "DAC")
      (value "PAD24AWG_PAD")
      (footprint "eagle-import:24AWG_PAD")
      (libsource (lib "eagle-import") (part "PAD24AWG_PAD"))
    )
    (comp (ref "DB")
      (value "PAD24AWG_PAD")
      (footprint "eagle-import:24AWG_PAD")
      (libsource (lib "eagle-import") (part "PAD24AWG_PAD"))
    )
    (comp (ref "DBG1")
      (value "PAD24AWG_PAD")
      (footprint "eagle-import:24AWG_PAD")
      (libsource (lib "eagle-import") (part "PAD24AWG_PAD"))
    )
    (comp (ref "DBG2")
      (value "PAD24AWG_PAD")
      (footprint "eagle-import:24AWG_PAD")
      (libsource (lib "eagle-import") (part "PAD24AWG_PAD"))
    )
    (comp (ref "DC")
      (value "PAD24AWG_PAD")
      (footprint "eagle-import:24AWG_PAD")
      (libsource (lib "eagle-import") (part "PAD24AWG_PAD"))
    )
    (comp (ref "DG1")
      (value "PAD24AWG_PAD")
      (footprint "eagle-import:24AWG_PAD")
      (libsource (lib "eagle-import") (part "PAD24AWG_PAD"))
    )
    (comp (ref "DG2")
      (value "PAD24AWG_PAD")
      (footprint "eagle-import:24AWG_PAD")
      (libsource (lib "eagle-import") (part "PAD24AWG_PAD"))
    )
    (comp (ref "DRV_CS")
      (value "PAD24AWG_PAD")
      (footprint "eagle-import:24AWG_PAD")
      (libsource (lib "eagle-import") (part "PAD24AWG_PAD"))
    )
    (comp (ref "DRV_MISO")
      (value "PAD24AWG_PAD")
      (footprint "eagle-import:24AWG_PAD")
      (libsource (lib "eagle-import") (part "PAD24AWG_PAD"))
    )
    (comp (ref "DRV_MOSI")
      (value "PAD24AWG_PAD")
      (footprint "eagle-import:24AWG_PAD")
      (libsource (lib "eagle-import") (part "PAD24AWG_PAD"))
    )
    (comp (ref "DRV_SCK")
      (value "PAD24AWG_PAD")
      (footprint "eagle-import:24AWG_PAD")
      (libsource (lib "eagle-import") (part "PAD24AWG_PAD"))
    )
    (comp (ref "DTR")
      (value "PAD24AWG_PAD")
      (footprint "eagle-import:24AWG_PAD")
      (libsource (lib "eagle-import") (part "PAD24AWG_PAD"))
    )
    (comp (ref "DTX")
      (value "PAD24AWG_PAD")
      (footprint "eagle-import:24AWG_PAD")
      (libsource (lib "eagle-import") (part "PAD24AWG_PAD"))
    )
    (comp (ref "ENC")
      (value "PICO-SPOX-6NOPASTE")
      (footprint "eagle-import:PICO-SPOX-SMT-RA-6-NOPASTE")
      (libsource (lib "eagle-import") (part "PICO-SPOX-6NOPASTE"))
    )
    (comp (ref "J1")
      (value "XT30XT30PW_MALE")
      (footprint "eagle-import:XT30PW_MALE")
      (libsource (lib "eagle-import") (part "XT30XT30PW_MALE"))
    )
    (comp (ref "J2")
      (value "XT30XT30PW_MALE")
      (footprint "eagle-import:XT30PW_MALE")
      (libsource (lib "eagle-import") (part "XT30XT30PW_MALE"))
    )
    (comp (ref "L1")
      (value "SRN4018-220M")
      (footprint "eagle-import:IND_BOURNS_SRN4018")
      (fields
        (field (name "MANUFACTURER_PART_NUMBER") "SRN4018220M")
        (field (name "MANUFACTURER_PART_NUMBER_1") "SRN4018-330M")
        (field (name "MPN") "SRN4018-330M")
      )
      (libsource (lib "eagle-import") (part "SRN4018-220M"))
    )
    (comp (ref "L2")
      (value "HALF_CHOKE")
      (footprint "eagle-import:1812_COMMON_HALF")
      (fields (field (name "MPN") "MF-RES-0805-0"))
      (libsource (lib "eagle-import") (part "HALF_CHOKE"))
    )
    (comp (ref "L3")
      (value "HALF_CHOKE")
      (footprint "eagle-import:1812_COMMON_HALF")
      (fields (field (name "MPN") "MF-RES-0805-0"))
      (libsource (lib "eagle-import") (part "HALF_CHOKE"))
    )
    (comp (ref "M1")
      (value "MOUNT")
      (footprint "eagle-import:M2.5MOUNT")
      (libsource (lib "eagle-import") (part "MOUNT"))
    )
    (comp (ref "M2")
      (value "MOUNT")
      (footprint "eagle-import:M2.5MOUNT")
      (libsource (lib "eagle-import") (part "MOUNT"))
    )
    (comp (ref "M3")
      (value "MOUNT")
      (footprint "eagle-import:M2.5MOUNT")
      (libsource (lib "eagle-import") (part "MOUNT"))
    )
    (comp (ref "M4")
      (value "MOUNT")
      (footprint "eagle-import:M2.5MOUNT")
      (libsource (lib "eagle-import") (part "MOUNT"))
    )
    (comp (ref "MOT1")
      (value "PAD24AWG_PAD")
      (footprint "eagle-import:24AWG_PAD")
      (libsource (lib "eagle-import") (part "PAD24AWG_PAD"))
    )
    (comp (ref "MOT2")
      (value "PAD24AWG_PAD")
      (footprint "eagle-import:24AWG_PAD")
      (libsource (lib "eagle-import") (part "PAD24AWG_PAD"))
    )
    (comp (ref "MOT3")
      (value "PAD24AWG_PAD")
      (footprint "eagle-import:24AWG_PAD")
      (libsource (lib "eagle-import") (part "PAD24AWG_PAD"))
    )
    (comp (ref "Q1")
      (value "TPH1R204PLSOP_ADVANCE_8")
      (footprint "eagle-import:SOP_ADVANCE_8")
      (fields
        (field (name "MF") "Toshiba")
        (field (name "MPN") "TPH1R204PL")
        (field (name "MF_1") "Toshiba")
        (field (name "MPN_1") "TPH2R506PL,L1Q")
      )
      (libsource (lib "eagle-import") (part "TPH1R204PLSOP_ADVANCE_8"))
    )
    (comp (ref "Q2")
      (value "TPH1R204PLSOP_ADVANCE_8")
      (footprint "eagle-import:SOP_ADVANCE_8")
      (fields
        (field (name "MF") "Toshiba")
        (field (name "MPN") "TPH1R204PL")
        (field (name "MF_1") "Toshiba")
        (field (name "MPN_1") "TPH2R506PL,L1Q")
      )
      (libsource (lib "eagle-import") (part "TPH1R204PLSOP_ADVANCE_8"))
    )
    (comp (ref "Q3")
      (value "TPH1R204PLSOP_ADVANCE_8")
      (footprint "eagle-import:SOP_ADVANCE_8")
      (fields
        (field (name "MF") "Toshiba")
        (field (name "MPN") "TPH1R204PL")
        (field (name "MF_1") "Toshiba")
        (field (name "MPN_1") "TPH2R506PL,L1Q")
      )
      (libsource (lib "eagle-import") (part "TPH1R204PLSOP_ADVANCE_8"))
    )
    (comp (ref "Q4")
      (value "TPH1R204PLSOP_ADVANCE_8")
      (footprint "eagle-import:SOP_ADVANCE_8")
      (fields
        (field (name "MF") "Toshiba")
        (field (name "MPN") "TPH1R204PL")
        (field (name "MF_1") "Toshiba")
        (field (name "MPN_1") "TPH2R506PL,L1Q")
      )
      (libsource (lib "eagle-import") (part "TPH1R204PLSOP_ADVANCE_8"))
    )
    (comp (ref "Q5")
      (value "TPH1R204PLSOP_ADVANCE_8")
      (footprint "eagle-import:SOP_ADVANCE_8")
      (fields
        (field (name "MF") "Toshiba")
        (field (name "MPN") "TPH1R204PL")
        (field (name "MF_1") "Toshiba")
        (field (name "MPN_1") "TPH2R506PL,L1Q")
      )
      (libsource (lib "eagle-import") (part "TPH1R204PLSOP_ADVANCE_8"))
    )
    (comp (ref "Q6")
      (value "TPH1R204PLSOP_ADVANCE_8")
      (footprint "eagle-import:SOP_ADVANCE_8")
      (fields
        (field (name "MF") "Toshiba")
        (field (name "MPN") "TPH1R204PL")
        (field (name "MF_1") "Toshiba")
        (field (name "MPN_1") "TPH2R506PL,L1Q")
      )
      (libsource (lib "eagle-import") (part "TPH1R204PLSOP_ADVANCE_8"))
    )
    (comp (ref "R1")
      (value "560")
      (footprint "eagle-import:R0402")
      (fields (field (name "HOUSEPART") "1") (field (name "MPN") "MF-RES-0402-560"))
      (libsource (lib "eagle-import") (part "RESISTOR_0402"))
    )
    (comp (ref "R2")
      (value "560")
      (footprint "eagle-import:R0402")
      (fields (field (name "HOUSEPART") "1") (field (name "MPN") "MF-RES-0402-560"))
      (libsource (lib "eagle-import") (part "RESISTOR_0402"))
    )
    (comp (ref "R3")
      (value "2k")
      (footprint "eagle-import:R0402")
      (fields (field (name "HOUSEPART") "YES") (field (name "MPN") "MF-RES-0402-2K"))
      (libsource (lib "eagle-import") (part "RESISTOR_0402"))
    )
    (comp (ref "R4")
      (value "2k")
      (footprint "eagle-import:R0402")
      (fields (field (name "HOUSEPART") "YES") (field (name "MPN") "MF-RES-0402-2K"))
      (libsource (lib "eagle-import") (part "RESISTOR_0402"))
    )
    (comp (ref "R5")
      (value "100k 1%")
      (footprint "eagle-import:R0402")
      (fields (field (name "MF") "Yageo") (field (name "MPN") "RC0402FR-07100KL"))
      (libsource (lib "eagle-import") (part "RESISTOR_0402"))
    )
    (comp (ref "R6")
      (value "4.7k 1%")
      (footprint "eagle-import:R0402")
      (fields (field (name "MF") "Yageo") (field (name "MPN") "RC0402FR-074K7L"))
      (libsource (lib "eagle-import") (part "RESISTOR_0402"))
    )
    (comp (ref "R7")
      (value "10k 1%")
      (footprint "eagle-import:R0402")
      (fields (field (name "MF") "Yageo") (field (name "MPN") "RC0402FR-0710KL"))
      (libsource (lib "eagle-import") (part "RESISTOR_0402"))
    )
    (comp (ref "R8")
      (value "47k NTC")
      (footprint "eagle-import:R0402")
      (fields (field (name "MF") "Murata") (field (name "MPN") "NCP15WB473F03RC"))
      (libsource (lib "eagle-import") (part "RESISTOR_0402"))
    )
    (comp (ref "R9")
      (value "10k 1%")
      (footprint "eagle-import:R0402")
      (fields (field (name "MF") "Yageo") (field (name "MPN") "RC0402FR-0710KL"))
      (libsource (lib "eagle-import") (part "RESISTOR_0402"))
    )
    (comp (ref "R10")
      (value "DNP")
      (footprint "eagle-import:R0402")
      (fields (field (name "POPULATE") "0"))
      (libsource (lib "eagle-import") (part "RESISTOR_0402"))
    )
    (comp (ref "R13")
      (value "2k")
      (footprint "eagle-import:R0402")
      (fields (field (name "HOUSEPART") "YES") (field (name "MPN") "MF-RES-0402-2K"))
      (libsource (lib "eagle-import") (part "RESISTOR_0402"))
    )
    (comp (ref "R14")
      (value "2k")
      (footprint "eagle-import:R0402")
      (fields (field (name "HOUSEPART") "YES") (field (name "MPN") "MF-RES-0402-2K"))
      (libsource (lib "eagle-import") (part "RESISTOR_0402"))
    )
    (comp (ref "R15")
      (value "22")
      (footprint "eagle-import:R0402")
      (fields (field (name "HOUSEPART") "1") (field (name "MPN") "MF-RES-0402-22"))
      (libsource (lib "eagle-import") (part "RESISTOR_0402"))
    )
    (comp (ref "R16")
      (value "22")
      (footprint "eagle-import:R0402")
      (fields (field (name "HOUSEPART") "1") (field (name "MPN") "MF-RES-0402-22"))
      (libsource (lib "eagle-import") (part "RESISTOR_0402"))
    )
    (comp (ref "R17")
      (value "22")
      (footprint "eagle-import:R0402")
      (fields (field (name "HOUSEPART") "1") (field (name "MPN") "MF-RES-0402-22"))
      (libsource (lib "eagle-import") (part "RESISTOR_0402"))
    )
    (comp (ref "RA")
      (value "0.5mOhm 1% 2W")
      (footprint "eagle-import:M1206")
      (fields (field (name "MF") "Stackpole Electronics") (field (name "MPN") "HCS1206FTL500"))
      (libsource (lib "eagle-import") (part "R-US_M1206"))
    )
    (comp (ref "RB")
      (value "0.5mOhm 1% 2W")
      (footprint "eagle-import:M1206")
      (fields (field (name "MF") "Stackpole Electronics") (field (name "MPN") "HCS1206FTL500"))
      (libsource (lib "eagle-import") (part "R-US_M1206"))
    )
    (comp (ref "RC")
      (value "0.5mOhm 1% 2W")
      (footprint "eagle-import:M1206")
      (fields (field (name "MF") "Stackpole Electronics") (field (name "MPN") "HCS1206FTL500"))
      (libsource (lib "eagle-import") (part "R-US_M1206"))
    )
    (comp (ref "SH1")
      (value "SHORTT5")
      (footprint "eagle-import:SHORT_TOP-50")
      (libsource (lib "eagle-import") (part "SHORTT5"))
    )
    (comp (ref "SH2")
      (value "SHORTT5")
      (footprint "eagle-import:SHORT_TOP-50")
      (libsource (lib "eagle-import") (part "SHORTT5"))
    )
    (comp (ref "SH3")
      (value "SHORTT5")
      (footprint "eagle-import:SHORT_TOP-50")
      (libsource (lib "eagle-import") (part "SHORTT5"))
    )
    (comp (ref "SH4")
      (value "SHORTMEDIUM")
      (footprint "eagle-import:SHORT_TOP-MEDIUM")
      (libsource (lib "eagle-import") (part "SHORTMEDIUM"))
    )
    (comp (ref "SWD")
      (value "JST-ZH6")
      (footprint "eagle-import:JST_S6B-ZR-SM4A-TF(LF)(SN)")
      (fields (field (name "MF") "JST") (field (name "MPN") "S6B-ZR-SM4A-TF(LF)(SN)"))
      (libsource (lib "eagle-import") (part "JST-ZH6"))
    )
    (comp (ref "TEMP1")
      (value "PAD24AWG_PAD")
      (footprint "eagle-import:24AWG_PAD")
      (libsource (lib "eagle-import") (part "PAD24AWG_PAD"))
    )
    (comp (ref "TEMP2")
      (value "PAD24AWG_PAD")
      (footprint "eagle-import:24AWG_PAD")
      (libsource (lib "eagle-import") (part "PAD24AWG_PAD"))
    )
    (comp (ref "U1")
      (value "STM32G474CEU6")
      (footprint "eagle-import:QFN50P700X700X60-49N")
      (fields (field (name "MOUSER_PART_NUMBER") "511-STM32G474CEU6"))
      (libsource (lib "eagle-import") (part "STM32G474CEU6"))
    )
    (comp (ref "U2")
      (value "TCAN334GSOT23")
      (footprint "eagle-import:SOT23-8")
      (fields (field (name "MF") "TI") (field (name "MPN") "TCAN334GDCNT"))
      (libsource (lib "eagle-import") (part "TCAN334GSOT23"))
    )
    (comp (ref "U3")
      (value "AS5147")
      (footprint "eagle-import:TSSOP14")
      (fields (field (name "MF") "AMS") (field (name "MPN") "AS5047P-ATSM"))
      (libsource (lib "eagle-import") (part "AS5147"))
    )
    (comp (ref "U4")
      (value "MAX15062AATA+T")
      (footprint "eagle-import:21-0487A_MXM")
      (fields (field (name "COPYRIGHT") "Copyright (C) 2018 Accelerated Designs. All rights reserved"))
      (libsource (lib "eagle-import") (part "MAX15062AATA+T"))
    )
    (comp (ref "U5")
      (value "DRV8353S")
      (footprint "eagle-import:WQFN-40")
      (fields (field (name "MF") "TI") (field (name "MPN") "DRV8353FSRTAR"))
      (libsource (lib "eagle-import") (part "DRV8353S"))
    )
  )
  (nets
    (net (code "1") (name "+3V3") (class "Default")
      (node (ref "ABS") (pin "1") (pinfunction "1_1") (pintype "passive"))
      (node (ref "C1") (pin "P$1") (pinfunction "P$1_P$1") (pintype "passive"))
      (node (ref "C10") (pin "P$1") (pinfunction "P$1_P$1") (pintype "passive"))
      (node (ref "C11") (pin "P$1") (pinfunction "P$1_P$1") (pintype "passive"))
      (node (ref "C12") (pin "P$1") (pinfunction "P$1_P$1") (pintype "passive"))
      (node (ref "C18") (pin "P$2") (pinfunction "P$2_P$2") (pintype "passive"))
      (node (ref "C2") (pin "P$1") (pinfunction "P$1_P$1") (pintype "passive"))
      (node (ref "C21") (pin "P$1") (pinfunction "P$1_P$1") (pintype "passive"))
      (node (ref "C4") (pin "P$1") (pinfunction "P$1_P$1") (pintype "passive"))
      (node (ref "C5") (pin "P$1") (pinfunction "P$1_P$1") (pintype "passive"))
      (node (ref "C56") (pin "P$1") (pinfunction "P$1_P$1") (pintype "passive"))
      (node (ref "C6") (pin "P$1") (pinfunction "P$1_P$1") (pintype "passive"))
      (node (ref "C7") (pin "P$2") (pinfunction "P$2_P$2") (pintype "passive"))
      (node (ref "C8") (pin "P$1") (pinfunction "P$1_P$1") (pintype "passive"))
      (node (ref "C9") (pin "P$1") (pinfunction "P$1_P$1") (pintype "passive"))
      (node (ref "D33") (pin "P$1") (pinfunction "P$1_P$1") (pintype "bidirectional"))
      (node (ref "ENC") (pin "1") (pinfunction "1_1") (pintype "passive"))
      (node (ref "L1") (pin "1") (pinfunction "1_1") (pintype "passive"))
      (node (ref "R1") (pin "P$1") (pinfunction "P$1_P$1") (pintype "passive"))
      (node (ref "R13") (pin "P$1") (pinfunction "P$1_P$1") (pintype "passive"))
      (node (ref "R14") (pin "P$1") (pinfunction "P$1_P$1") (pintype "passive"))
      (node (ref "R2") (pin "P$1") (pinfunction "P$1_P$1") (pintype "passive"))
      (node (ref "R3") (pin "P$1") (pinfunction "P$1_P$1") (pintype "passive"))
      (node (ref "R4") (pin "P$1") (pinfunction "P$1_P$1") (pintype "passive"))
      (node (ref "R8") (pin "P$1") (pinfunction "P$1_P$1") (pintype "passive"))
      (node (ref "SWD") (pin "6") (pinfunction "6_6") (pintype "passive"))
      (node (ref "TEMP1") (pin "P$1") (pinfunction "P$1_P$1") (pintype "bidirectional"))
      (node (ref "U1") (pin "1") (pinfunction "VBAT_1") (pintype "bidirectional"))
      (node (ref "U1") (pin "20") (pinfunction "VREF+_20") (pintype "bidirectional"))
      (node (ref "U1") (pin "21") (pinfunction "VDDA_21") (pintype "bidirectional"))
      (node (ref "U1") (pin "23") (pinfunction "VDD_1_23") (pintype "bidirectional"))
      (node (ref "U1") (pin "35") (pinfunction "VDD_2_35") (pintype "bidirectional"))
      (node (ref "U1") (pin "48") (pinfunction "VDD_3_48") (pintype "bidirectional"))
      (node (ref "U2") (pin "3") (pinfunction "VCC_3") (pintype "power_in"))
      (node (ref "U3") (pin "12") (pinfunction "VDD3V_12") (pintype "bidirectional"))
      (node (ref "U4") (pin "4") (pinfunction "FB/VOUT_4") (pintype "bidirectional"))
      (node (ref "U5") (pin "24") (pinfunction "VREF_24") (pintype "bidirectional"))
    )
    (net (code "2") (name "/AS5047_A") (class "Default")
      (node (ref "U1") (pin "43") (pinfunction "PB5_43") (pintype "bidirectional"))
      (node (ref "U3") (pin "7") (pinfunction "A_7") (pintype "bidirectional"))
    )
    (net (code "3") (name "/AS5047_B") (class "Default")
      (node (ref "U1") (pin "42") (pinfunction "PB4_42") (pintype "bidirectional"))
      (node (ref "U3") (pin "6") (pinfunction "B_6") (pintype "bidirectional"))
    )
    (net (code "4") (name "/AS5047_CS") (class "Default")
      (node (ref "U1") (pin "24") (pinfunction "PB11_24") (pintype "bidirectional"))
      (node (ref "U3") (pin "1") (pinfunction "CS/_1") (pintype "bidirectional"))
    )
    (net (code "5") (name "/AS5047_MISO") (class "Default")
      (node (ref "ENC") (pin "5") (pinfunction "5_5") (pintype "passive"))
      (node (ref "U1") (pin "27") (pinfunction "PB14_27") (pintype "bidirectional"))
      (node (ref "U3") (pin "3") (pinfunction "MISO_3") (pintype "bidirectional"))
    )
    (net (code "6") (name "/AS5047_MOSI") (class "Default")
      (node (ref "ENC") (pin "6") (pinfunction "6_6") (pintype "passive"))
      (node (ref "U1") (pin "28") (pinfunction "PB15_28") (pintype "bidirectional"))
      (node (ref "U3") (pin "4") (pinfunction "MOSI_4") (pintype "bidirectional"))
    )
    (net (code "7") (name "/AS5047_SCK") (class "Default")
      (node (ref "ENC") (pin "4") (pinfunction "4_4") (pintype "passive"))
      (node (ref "U1") (pin "26") (pinfunction "PB13_26") (pintype "bidirectional"))
      (node (ref "U3") (pin "2") (pinfunction "CLK_2") (pintype "bidirectional"))
    )
    (net (code "8") (name "/CAN2_N") (class "Default")
      (node (ref "L2") (pin "P$2") (pinfunction "2_P$2") (pintype "passive"))
      (node (ref "U2") (pin "6") (pinfunction "CANL_6") (pintype "bidirectional"))
    )
    (net (code "9") (name "/CAN2_P") (class "Default")
      (node (ref "L3") (pin "P$2") (pinfunction "2_P$2") (pintype "passive"))
      (node (ref "U2") (pin "7") (pinfunction "CANH_7") (pintype "bidirectional"))
    )
    (net (code "10") (name "/CAN_N") (class "Default")
      (node (ref "CAN1") (pin "2") (pinfunction "2_2") (pintype "passive"))
      (node (ref "CAN2") (pin "2") (pinfunction "2_2") (pintype "passive"))
      (node (ref "D4") (pin "2") (pinfunction "2_2") (pintype "bidirectional"))
      (node (ref "L2") (pin "P$1") (pinfunction "1_P$1") (pintype "passive"))
    )
    (net (code "11") (name "/CAN_P") (class "Default")
      (node (ref "CAN1") (pin "1") (pinfunction "1_1") (pintype "passive"))
      (node (ref "CAN2") (pin "1") (pinfunction "1_1") (pintype "passive"))
      (node (ref "D4") (pin "1") (pinfunction "1_1") (pintype "bidirectional"))
      (node (ref "L3") (pin "P$1") (pinfunction "1_P$1") (pintype "passive"))
    )
    (net (code "12") (name "/CAN_RX") (class "Default")
      (node (ref "U1") (pin "33") (pinfunction "PA11_33") (pintype "bidirectional"))
      (node (ref "U2") (pin "4") (pinfunction "RXD_4") (pintype "output"))
    )
    (net (code "13") (name "/CAN_TX") (class "Default")
      (node (ref "U1") (pin "34") (pinfunction "PA12_34") (pintype "bidirectional"))
      (node (ref "U2") (pin "1") (pinfunction "TXD_1") (pintype "input"))
    )
    (net (code "14") (name "/CUR1") (class "Default")
      (node (ref "R15") (pin "P$1") (pinfunction "P$1_P$1") (pintype "passive"))
      (node (ref "U5") (pin "23") (pinfunction "SOA_23") (pintype "bidirectional"))
    )
    (net (code "15") (name "/CUR2") (class "Default")
      (node (ref "R16") (pin "P$1") (pinfunction "P$1_P$1") (pintype "passive"))
      (node (ref "U5") (pin "22") (pinfunction "SOB_22") (pintype "bidirectional"))
    )
    (net (code "16") (name "/CUR3") (class "Default")
      (node (ref "R17") (pin "P$1") (pinfunction "P$1_P$1") (pintype "passive"))
      (node (ref "U5") (pin "21") (pinfunction "SOC_21") (pintype "bidirectional"))
    )
    (net (code "17") (name "/DAC") (class "Default")
      (node (ref "DAC") (pin "P$1") (pinfunction "P$1_P$1") (pintype "bidirectional"))
      (node (ref "U1") (pin "12") (pinfunction "PA4_12") (pintype "bidirectional"))
    )
    (net (code "18") (name "/DEBUG1") (class "Default")
      (node (ref "DBG1") (pin "P$1") (pinfunction "P$1_P$1") (pintype "bidirectional"))
      (node (ref "U1") (pin "3") (pinfunction "PC14-OSC32_IN_3") (pintype "bidirectional"))
    )
    (net (code "19") (name "/DEBUG2") (class "Default")
      (node (ref "DBG2") (pin "P$1") (pinfunction "P$1_P$1") (pintype "bidirectional"))
      (node (ref "U1") (pin "4") (pinfunction "PC15-OSC32_OUT_4") (pintype "bidirectional"))
    )
    (net (code "20") (name "/DEBUG_RX") (class "Default")
      (node (ref "DTR") (pin "P$1") (pinfunction "P$1_P$1") (pintype "bidirectional"))
      (node (ref "U1") (pin "40") (pinfunction "PC11_40") (pintype "bidirectional"))
    )
    (net (code "21") (name "/DEBUG_TX") (class "Default")
      (node (ref "DTX") (pin "P$1") (pinfunction "P$1_P$1") (pintype "bidirectional"))
      (node (ref "U1") (pin "39") (pinfunction "PC10_39") (pintype "bidirectional"))
    )
    (net (code "22") (name "/DRV8323_CS") (class "Default")
      (node (ref "DRV_CS") (pin "P$1") (pinfunction "P$1_P$1") (pintype "bidirectional"))
      (node (ref "U1") (pin "16") (pinfunction "PC4_16") (pintype "bidirectional"))
      (node (ref "U5") (pin "30") (pinfunction "CS_30") (pintype "bidirectional"))
    )
    (net (code "23") (name "/DRV8323_MISO") (class "Default")
      (node (ref "DRV_MISO") (pin "P$1") (pinfunction "P$1_P$1") (pintype "bidirectional"))
      (node (ref "R13") (pin "P$2") (pinfunction "P$2_P$2") (pintype "passive"))
      (node (ref "U1") (pin "14") (pinfunction "PA6_14") (pintype "bidirectional"))
      (node (ref "U5") (pin "27") (pinfunction "MISO_27") (pintype "bidirectional"))
    )
    (net (code "24") (name "/DRV8323_MOSI") (class "Default")
      (node (ref "DRV_MOSI") (pin "P$1") (pinfunction "P$1_P$1") (pintype "bidirectional"))
      (node (ref "U1") (pin "15") (pinfunction "PA7_15") (pintype "bidirectional"))
      (node (ref "U5") (pin "28") (pinfunction "MOSI_28") (pintype "bidirectional"))
    )
    (net (code "25") (name "/DRV8323_SCLK") (class "Default")
      (node (ref "DRV_SCK") (pin "P$1") (pinfunction "P$1_P$1") (pintype "bidirectional"))
      (node (ref "U1") (pin "13") (pinfunction "PA5_13") (pintype "bidirectional"))
      (node (ref "U5") (pin "29") (pinfunction "SCLK_29") (pintype "bidirectional"))
    )
    (net (code "26") (name "/FCUR1") (class "Default")
      (node (ref "C58") (pin "P$1") (pinfunction "P$1_P$1") (pintype "passive"))
      (node (ref "R15") (pin "P$2") (pinfunction "P$2_P$2") (pintype "passive"))
      (node (ref "U1") (pin "17") (pinfunction "PB0_17") (pintype "bidirectional"))
    )
    (net (code "27") (name "/FCUR2") (class "Default")
      (node (ref "C59") (pin "P$1") (pinfunction "P$1_P$1") (pintype "passive"))
      (node (ref "R16") (pin "P$2") (pinfunction "P$2_P$2") (pintype "passive"))
      (node (ref "U1") (pin "18") (pinfunction "PB1_18") (pintype "bidirectional"))
    )
    (net (code "28") (name "/FCUR3") (class "Default")
      (node (ref "C60") (pin "P$1") (pinfunction "P$1_P$1") (pintype "passive"))
      (node (ref "R17") (pin "P$2") (pinfunction "P$2_P$2") (pintype "passive"))
      (node (ref "U1") (pin "19") (pinfunction "PB2_19") (pintype "bidirectional"))
    )
    (net (code "29") (name "/GHA") (class "Default")
      (node (ref "Q1") (pin "4") (pinfunction "G_4") (pintype "passive"))
      (node (ref "U5") (pin "6") (pinfunction "GHA_6") (pintype "bidirectional"))
    )
    (net (code "30") (name "/GHB") (class "Default")
      (node (ref "Q3") (pin "4") (pinfunction "G_4") (pintype "passive"))
      (node (ref "U5") (pin "15") (pinfunction "GHB_15") (pintype "bidirectional"))
    )
    (net (code "31") (name "/GHC") (class "Default")
      (node (ref "Q5") (pin "4") (pinfunction "G_4") (pintype "passive"))
      (node (ref "U5") (pin "16") (pinfunction "GHC_16") (pintype "bidirectional"))
    )
    (net (code "32") (name "/GLA") (class "Default")
      (node (ref "Q2") (pin "4") (pinfunction "G_4") (pintype "passive"))
      (node (ref "U5") (pin "8") (pinfunction "GLA_8") (pintype "bidirectional"))
    )
    (net (code "33") (name "/GLB") (class "Default")
      (node (ref "Q4") (pin "4") (pinfunction "G_4") (pintype "passive"))
      (node (ref "U5") (pin "13") (pinfunction "GLB_13") (pintype "bidirectional"))
    )
    (net (code "34") (name "/GLC") (class "Default")
      (node (ref "Q6") (pin "4") (pinfunction "G_4") (pintype "passive"))
      (node (ref "U5") (pin "18") (pinfunction "GLC_18") (pintype "bidirectional"))
    )
    (net (code "35") (name "/I2C_ABS_SCL") (class "Default")
      (node (ref "ABS") (pin "2") (pinfunction "2_2") (pintype "passive"))
      (node (ref "R4") (pin "P$2") (pinfunction "P$2_P$2") (pintype "passive"))
      (node (ref "U1") (pin "46") (pinfunction "PB8-BOOT0_46") (pintype "bidirectional"))
    )
    (net (code "36") (name "/I2C_ABS_SDA") (class "Default")
      (node (ref "ABS") (pin "3") (pinfunction "3_3") (pintype "passive"))
      (node (ref "R3") (pin "P$2") (pinfunction "P$2_P$2") (pintype "passive"))
      (node (ref "U1") (pin "47") (pinfunction "PB9_47") (pintype "bidirectional"))
    )
    (net (code "37") (name "/LED1") (class "Default")
      (node (ref "D3") (pin "CATHODE") (pinfunction "CATHODE_CATHODE") (pintype "power_in"))
      (node (ref "U1") (pin "5") (pinfunction "PF0-OSC_IN_5") (pintype "bidirectional"))
    )
    (net (code "38") (name "/LED2") (class "Default")
      (node (ref "D2") (pin "CATHODE") (pinfunction "CATHODE_CATHODE") (pintype "power_in"))
      (node (ref "U1") (pin "6") (pinfunction "PF1-OSC_OUT_6") (pintype "bidirectional"))
    )
    (net (code "39") (name "/MOTOR1") (class "Default")
      (node (ref "MOT1") (pin "P$1") (pinfunction "P$1_P$1") (pintype "bidirectional"))
      (node (ref "U1") (pin "8") (pinfunction "PA0_8") (pintype "bidirectional"))
      (node (ref "U5") (pin "32") (pinfunction "INHA_32") (pintype "bidirectional"))
    )
    (net (code "40") (name "/MOTOR2") (class "Default")
      (node (ref "MOT2") (pin "P$1") (pinfunction "P$1_P$1") (pintype "bidirectional"))
      (node (ref "U1") (pin "9") (pinfunction "PA1_9") (pintype "bidirectional"))
      (node (ref "U5") (pin "34") (pinfunction "INHB_34") (pintype "bidirectional"))
    )
    (net (code "41") (name "/MOTOR3") (class "Default")
      (node (ref "MOT3") (pin "P$1") (pinfunction "P$1_P$1") (pintype "bidirectional"))
      (node (ref "U1") (pin "10") (pinfunction "PA2_10") (pintype "bidirectional"))
      (node (ref "U5") (pin "36") (pinfunction "INHC_36") (pintype "bidirectional"))
    )
    (net (code "42") (name "/MOTOR_ENABLE") (class "Default")
      (node (ref "U1") (pin "11") (pinfunction "PA3_11") (pintype "bidirectional"))
      (node (ref "U5") (pin "31") (pinfunction "ENABLE_31") (pintype "bidirectional"))
    )
    (net (code "43") (name "/MOTOR_FAULT") (class "Default")
      (node (ref "R14") (pin "P$2") (pinfunction "P$2_P$2") (pintype "passive"))
      (node (ref "U1") (pin "44") (pinfunction "PB6_44") (pintype "bidirectional"))
      (node (ref "U5") (pin "26") (pinfunction "FAULT_26") (pintype "bidirectional"))
    )
    (net (code "44") (name "/MOTOR_HIZ") (class "Default")
      (node (ref "U1") (pin "45") (pinfunction "PB7_45") (pintype "bidirectional"))
      (node (ref "U5") (pin "33") (pinfunction "INLA_33") (pintype "bidirectional"))
      (node (ref "U5") (pin "35") (pinfunction "INLB_35") (pintype "bidirectional"))
      (node (ref "U5") (pin "37") (pinfunction "INLC_37") (pintype "bidirectional"))
    )
    (net (code "45") (name "/NRST") (class "Default")
      (node (ref "C3") (pin "P$1") (pinfunction "P$1_P$1") (pintype "passive"))
      (node (ref "SWD") (pin "2") (pinfunction "2_2") (pintype "passive"))
      (node (ref "U1") (pin "7") (pinfunction "PG10-NRST_7") (pintype "bidirectional"))
    )
    (net (code "46") (name "/SECONDARY_ENC_CS") (class "Default")
      (node (ref "ENC") (pin "2") (pinfunction "2_2") (pintype "passive"))
      (node (ref "U1") (pin "2") (pinfunction "PC13_2") (pintype "bidirectional"))
    )
    (net (code "47") (name "/SHA") (class "Default")
      (node (ref "A") (pin "1") (pinfunction "P$1_1") (pintype "bidirectional"))
      (node (ref "DA") (pin "P$1") (pinfunction "P$1_P$1") (pintype "bidirectional"))
      (node (ref "Q1") (pin "1") (pinfunction "S_1") (pintype "passive"))
      (node (ref "Q1") (pin "2") (pinfunction "S_2") (pintype "passive"))
      (node (ref "Q1") (pin "3") (pinfunction "S_3") (pintype "passive"))
      (node (ref "Q2") (pin "5") (pinfunction "D_5") (pintype "passive"))
      (node (ref "Q2") (pin "6") (pinfunction "D_6") (pintype "passive"))
      (node (ref "Q2") (pin "7") (pinfunction "D_7") (pintype "passive"))
      (node (ref "Q2") (pin "8") (pinfunction "D_8") (pintype "passive"))
      (node (ref "Q2") (pin "PAD") (pinfunction "D_PAD") (pintype "passive"))
      (node (ref "U5") (pin "7") (pinfunction "SHA_7") (pintype "bidirectional"))
    )
    (net (code "48") (name "/SHB") (class "Default")
      (node (ref "B") (pin "1") (pinfunction "P$1_1") (pintype "bidirectional"))
      (node (ref "DB") (pin "P$1") (pinfunction "P$1_P$1") (pintype "bidirectional"))
      (node (ref "Q3") (pin "1") (pinfunction "S_1") (pintype "passive"))
      (node (ref "Q3") (pin "2") (pinfunction "S_2") (pintype "passive"))
      (node (ref "Q3") (pin "3") (pinfunction "S_3") (pintype "passive"))
      (node (ref "Q4") (pin "5") (pinfunction "D_5") (pintype "passive"))
      (node (ref "Q4") (pin "6") (pinfunction "D_6") (pintype "passive"))
      (node (ref "Q4") (pin "7") (pinfunction "D_7") (pintype "passive"))
      (node (ref "Q4") (pin "8") (pinfunction "D_8") (pintype "passive"))
      (node (ref "Q4") (pin "PAD") (pinfunction "D_PAD") (pintype "passive"))
      (node (ref "U5") (pin "14") (pinfunction "SHB_14") (pintype "bidirectional"))
    )
    (net (code "49") (name "/SHC") (class "Default")
      (node (ref "C") (pin "1") (pinfunction "P$1_1") (pintype "bidirectional"))
      (node (ref "DC") (pin "P$1") (pinfunction "P$1_P$1") (pintype "bidirectional"))
      (node (ref "Q5") (pin "1") (pinfunction "S_1") (pintype "passive"))
      (node (ref "Q5") (pin "2") (pinfunction "S_2") (pintype "passive"))
      (node (ref "Q5") (pin "3") (pinfunction "S_3") (pintype "passive"))
      (node (ref "Q6") (pin "5") (pinfunction "D_5") (pintype "passive"))
      (node (ref "Q6") (pin "6") (pinfunction "D_6") (pintype "passive"))
      (node (ref "Q6") (pin "7") (pinfunction "D_7") (pintype "passive"))
      (node (ref "Q6") (pin "8") (pinfunction "D_8") (pintype "passive"))
      (node (ref "Q6") (pin "PAD") (pinfunction "D_PAD") (pintype "passive"))
      (node (ref "U5") (pin "17") (pinfunction "SHC_17") (pintype "bidirectional"))
    )
    (net (code "50") (name "/SWCLK") (class "Default")
      (node (ref "SWD") (pin "5") (pinfunction "5_5") (pintype "passive"))
      (node (ref "U1") (pin "37") (pinfunction "PA14_37") (pintype "bidirectional"))
    )
    (net (code "51") (name "/SWDIO") (class "Default")
      (node (ref "SWD") (pin "3") (pinfunction "3_3") (pintype "passive"))
      (node (ref "U1") (pin "36") (pinfunction "PA13_36") (pintype "bidirectional"))
    )
    (net (code "52") (name "/SXA_N") (class "Default")
      (node (ref "SH1") (pin "1") (pinfunction "P$1_1") (pintype "bidirectional"))
      (node (ref "U5") (pin "10") (pinfunction "SNA_10") (pintype "bidirectional"))
    )
    (net (code "53") (name "/SXA_P") (class "Default")
      (node (ref "Q2") (pin "1") (pinfunction "S_1") (pintype "passive"))
      (node (ref "Q2") (pin "2") (pinfunction "S_2") (pintype "passive"))
      (node (ref "Q2") (pin "3") (pinfunction "S_3") (pintype "passive"))
      (node (ref "RA") (pin "2") (pinfunction "2_2") (pintype "passive"))
      (node (ref "U5") (pin "9") (pinfunction "SPA_9") (pintype "bidirectional"))
    )
    (net (code "54") (name "/SXB_N") (class "Default")
      (node (ref "SH2") (pin "1") (pinfunction "P$1_1") (pintype "bidirectional"))
      (node (ref "U5") (pin "11") (pinfunction "SNB_11") (pintype "bidirectional"))
    )
    (net (code "55") (name "/SXB_P") (class "Default")
      (node (ref "Q4") (pin "1") (pinfunction "S_1") (pintype "passive"))
      (node (ref "Q4") (pin "2") (pinfunction "S_2") (pintype "passive"))
      (node (ref "Q4") (pin "3") (pinfunction "S_3") (pintype "passive"))
      (node (ref "RB") (pin "2") (pinfunction "2_2") (pintype "passive"))
      (node (ref "U5") (pin "12") (pinfunction "SPB_12") (pintype "bidirectional"))
    )
    (net (code "56") (name "/SXC_N") (class "Default")
      (node (ref "SH3") (pin "1") (pinfunction "P$1_1") (pintype "bidirectional"))
      (node (ref "U5") (pin "20") (pinfunction "SNC_20") (pintype "bidirectional"))
    )
    (net (code "57") (name "/SXC_P") (class "Default")
      (node (ref "Q6") (pin "1") (pinfunction "S_1") (pintype "passive"))
      (node (ref "Q6") (pin "2") (pinfunction "S_2") (pintype "passive"))
      (node (ref "Q6") (pin "3") (pinfunction "S_3") (pintype "passive"))
      (node (ref "RC") (pin "2") (pinfunction "2_2") (pintype "passive"))
      (node (ref "U5") (pin "19") (pinfunction "SPC_19") (pintype "bidirectional"))
    )
    (net (code "58") (name "/VBAT_SENSE") (class "Default")
      (node (ref "C57") (pin "P$1") (pinfunction "P$1_P$1") (pintype "passive"))
      (node (ref "R5") (pin "P$1") (pinfunction "P$1_P$1") (pintype "passive"))
      (node (ref "R6") (pin "P$2") (pinfunction "P$2_P$2") (pintype "passive"))
      (node (ref "U1") (pin "25") (pinfunction "PB12_25") (pintype "bidirectional"))
    )
    (net (code "59") (name "/VSW") (class "Default")
      (node (ref "L1") (pin "2") (pinfunction "2_2") (pintype "passive"))
      (node (ref "U4") (pin "8") (pinfunction "LX_8") (pintype "passive"))
    )
    (net (code "60") (name "/VTEMP_FET") (class "Default")
      (node (ref "C13") (pin "P$1") (pinfunction "P$1_P$1") (pintype "passive"))
      (node (ref "R8") (pin "P$2") (pinfunction "P$2_P$2") (pintype "passive"))
      (node (ref "R9") (pin "P$1") (pinfunction "P$1_P$1") (pintype "passive"))
      (node (ref "U1") (pin "31") (pinfunction "PA9_31") (pintype "bidirectional"))
    )
    (net (code "61") (name "/VTEMP_MOT") (class "Default")
      (node (ref "R7") (pin "P$1") (pinfunction "P$1_P$1") (pintype "passive"))
      (node (ref "TEMP2") (pin "P$1") (pinfunction "P$1_P$1") (pintype "bidirectional"))
      (node (ref "U1") (pin "30") (pinfunction "PA8_30") (pintype "bidirectional"))
    )
    (net (code "62") (name "GND") (class "Default")
      (node (ref "ABS") (pin "4") (pinfunction "4_4") (pintype "passive"))
      (node (ref "C1") (pin "P$2") (pinfunction "P$2_P$2") (pintype "passive"))
      (node (ref "C10") (pin "P$2") (pinfunction "P$2_P$2") (pintype "passive"))
      (node (ref "C11") (pin "P$2") (pinfunction "P$2_P$2") (pintype "passive"))
      (node (ref "C12") (pin "P$2") (pinfunction "P$2_P$2") (pintype "passive"))
      (node (ref "C13") (pin "P$2") (pinfunction "P$2_P$2") (pintype "passive"))
      (node (ref "C18") (pin "P$1") (pinfunction "P$1_P$1") (pintype "passive"))
      (node (ref "C2") (pin "P$2") (pinfunction "P$2_P$2") (pintype "passive"))
      (node (ref "C20") (pin "P$2") (pinfunction "P$2_P$2") (pintype "passive"))
      (node (ref "C21") (pin "P$2") (pinfunction "P$2_P$2") (pintype "passive"))
      (node (ref "C3") (pin "P$2") (pinfunction "P$2_P$2") (pintype "passive"))
      (node (ref "C4") (pin "P$2") (pinfunction "P$2_P$2") (pintype "passive"))
      (node (ref "C5") (pin "P$2") (pinfunction "P$2_P$2") (pintype "passive"))
      (node (ref "C56") (pin "P$2") (pinfunction "P$2_P$2") (pintype "passive"))
      (node (ref "C57") (pin "P$2") (pinfunction "P$2_P$2") (pintype "passive"))
      (node (ref "C58") (pin "P$2") (pinfunction "P$2_P$2") (pintype "passive"))
      (node (ref "C59") (pin "P$2") (pinfunction "P$2_P$2") (pintype "passive"))
      (node (ref "C6") (pin "P$2") (pinfunction "P$2_P$2") (pintype "passive"))
      (node (ref "C60") (pin "P$2") (pinfunction "P$2_P$2") (pintype "passive"))
      (node (ref "C7") (pin "P$1") (pinfunction "P$1_P$1") (pintype "passive"))
      (node (ref "C8") (pin "P$2") (pinfunction "P$2_P$2") (pintype "passive"))
      (node (ref "C9") (pin "P$2") (pinfunction "P$2_P$2") (pintype "passive"))
      (node (ref "CAN1") (pin "3") (pinfunction "3_3") (pintype "passive"))
      (node (ref "CAN2") (pin "3") (pinfunction "3_3") (pintype "passive"))
      (node (ref "D4") (pin "3") (pinfunction "3_3") (pintype "bidirectional"))
      (node (ref "DG1") (pin "P$1") (pinfunction "P$1_P$1") (pintype "bidirectional"))
      (node (ref "DG2") (pin "P$1") (pinfunction "P$1_P$1") (pintype "bidirectional"))
      (node (ref "ENC") (pin "3") (pinfunction "3_3") (pintype "passive"))
      (node (ref "R6") (pin "P$1") (pinfunction "P$1_P$1") (pintype "passive"))
      (node (ref "R7") (pin "P$2") (pinfunction "P$2_P$2") (pintype "passive"))
      (node (ref "R9") (pin "P$2") (pinfunction "P$2_P$2") (pintype "passive"))
      (node (ref "SH4") (pin "2") (pinfunction "P$2_2") (pintype "bidirectional"))
      (node (ref "SWD") (pin "4") (pinfunction "4_4") (pintype "passive"))
      (node (ref "U1") (pin "29") (pinfunction "PC6_29") (pintype "bidirectional"))
      (node (ref "U1") (pin "38") (pinfunction "PA15_38") (pintype "bidirectional"))
      (node (ref "U1") (pin "49") (pinfunction "THERMALPAD_49") (pintype "bidirectional"))
      (node (ref "U2") (pin "2") (pinfunction "GND_2") (pintype "power_in"))
      (node (ref "U2") (pin "5") (pinfunction "SHDN_5") (pintype "input"))
      (node (ref "U2") (pin "8") (pinfunction "STB_8") (pintype "input"))
      (node (ref "U3") (pin "13") (pinfunction "GND_13") (pintype "bidirectional"))
      (node (ref "U3") (pin "5") (pinfunction "TEST_5") (pintype "bidirectional"))
      (node (ref "U4") (pin "7") (pinfunction "GND_7") (pintype "power_in"))
      (node (ref "U5") (pin "25") (pinfunction "AGND_25") (pintype "bidirectional"))
    )
    (net (code "63") (name "Net-(C55-PadP$1)") (class "Default")
      (node (ref "C55") (pin "P$1") (pinfunction "P$1_P$1") (pintype "passive"))
      (node (ref "M3") (pin "P$1") (pinfunction "P$1_P$1") (pintype "bidirectional"))
      (node (ref "R10") (pin "P$1") (pinfunction "P$1_P$1") (pintype "passive"))
    )
    (net (code "64") (name "Net-(D2-PadANODE)") (class "Default")
      (node (ref "D2") (pin "ANODE") (pinfunction "ANODE_ANODE") (pintype "power_in"))
      (node (ref "R2") (pin "P$2") (pinfunction "P$2_P$2") (pintype "passive"))
    )
    (net (code "65") (name "Net-(D3-PadANODE)") (class "Default")
      (node (ref "D3") (pin "ANODE") (pinfunction "ANODE_ANODE") (pintype "power_in"))
      (node (ref "R1") (pin "P$2") (pinfunction "P$2_P$2") (pintype "passive"))
    )
    (net (code "66") (name "Net-(U4-VCC)") (class "Default")
      (node (ref "C20") (pin "P$1") (pinfunction "P$1_P$1") (pintype "passive"))
      (node (ref "U4") (pin "3") (pinfunction "VCC_3") (pintype "power_in"))
    )
    (net (code "67") (name "Net-(U5-CPH)") (class "Default")
      (node (ref "C16") (pin "P$1") (pinfunction "P$1_P$1") (pintype "passive"))
      (node (ref "U5") (pin "2") (pinfunction "CPH_2") (pintype "bidirectional"))
    )
    (net (code "68") (name "Net-(U5-CPL)") (class "Default")
      (node (ref "C16") (pin "P$2") (pinfunction "P$2_P$2") (pintype "passive"))
      (node (ref "U5") (pin "1") (pinfunction "CPL_1") (pintype "bidirectional"))
    )
    (net (code "69") (name "Net-(U5-DVDD)") (class "Default")
      (node (ref "C17") (pin "P$2") (pinfunction "P$2_P$2") (pintype "passive"))
      (node (ref "U5") (pin "38") (pinfunction "DVDD_38") (pintype "bidirectional"))
    )
    (net (code "70") (name "Net-(U5-VCP)") (class "Default")
      (node (ref "C15") (pin "P$2") (pinfunction "P$2_P$2") (pintype "passive"))
      (node (ref "U5") (pin "5") (pinfunction "VCP_5") (pintype "bidirectional"))
    )
    (net (code "71") (name "Net-(U5-VGLS)") (class "Default")
      (node (ref "C38") (pin "P$2") (pinfunction "P$2_P$2") (pintype "passive"))
      (node (ref "U5") (pin "40") (pinfunction "VGLS_40") (pintype "bidirectional"))
    )
    (net (code "72") (name "V+") (class "Default")
      (node (ref "C14") (pin "P$1") (pinfunction "P$1_P$1") (pintype "passive"))
      (node (ref "C15") (pin "P$1") (pinfunction "P$1_P$1") (pintype "passive"))
      (node (ref "C19") (pin "P$1") (pinfunction "P$1_P$1") (pintype "passive"))
      (node (ref "C22") (pin "P$1") (pinfunction "P$1_P$1") (pintype "passive"))
      (node (ref "C23") (pin "P$1") (pinfunction "P$1_P$1") (pintype "passive"))
      (node (ref "C24") (pin "P$1") (pinfunction "P$1_P$1") (pintype "passive"))
      (node (ref "C25") (pin "P$1") (pinfunction "P$1_P$1") (pintype "passive"))
      (node (ref "C26") (pin "P$1") (pinfunction "P$1_P$1") (pintype "passive"))
      (node (ref "C27") (pin "P$1") (pinfunction "P$1_P$1") (pintype "passive"))
      (node (ref "C28") (pin "P$1") (pinfunction "P$1_P$1") (pintype "passive"))
      (node (ref "C29") (pin "P$1") (pinfunction "P$1_P$1") (pintype "passive"))
      (node (ref "C30") (pin "P$1") (pinfunction "P$1_P$1") (pintype "passive"))
      (node (ref "C31") (pin "P$1") (pinfunction "P$1_P$1") (pintype "passive"))
      (node (ref "C32") (pin "P$1") (pinfunction "P$1_P$1") (pintype "passive"))
      (node (ref "C33") (pin "P$1") (pinfunction "P$1_P$1") (pintype "passive"))
      (node (ref "C34") (pin "P$1") (pinfunction "P$1_P$1") (pintype "passive"))
      (node (ref "C35") (pin "P$1") (pinfunction "P$1_P$1") (pintype "passive"))
      (node (ref "C36") (pin "P$1") (pinfunction "P$1_P$1") (pintype "passive"))
      (node (ref "C37") (pin "P$1") (pinfunction "P$1_P$1") (pintype "passive"))
      (node (ref "C39") (pin "P$1") (pinfunction "P$1_P$1") (pintype "passive"))
      (node (ref "C40") (pin "P$1") (pinfunction "P$1_P$1") (pintype "passive"))
      (node (ref "C41") (pin "P$1") (pinfunction "P$1_P$1") (pintype "passive"))
      (node (ref "C42") (pin "P$1") (pinfunction "P$1_P$1") (pintype "passive"))
      (node (ref "C43") (pin "P$1") (pinfunction "P$1_P$1") (pintype "passive"))
      (node (ref "C44") (pin "P$1") (pinfunction "P$1_P$1") (pintype "passive"))
      (node (ref "C45") (pin "P$1") (pinfunction "P$1_P$1") (pintype "passive"))
      (node (ref "C46") (pin "P$1") (pinfunction "P$1_P$1") (pintype "passive"))
      (node (ref "C47") (pin "P$1") (pinfunction "P$1_P$1") (pintype "passive"))
      (node (ref "C48") (pin "P$1") (pinfunction "P$1_P$1") (pintype "passive"))
      (node (ref "C49") (pin "P$1") (pinfunction "P$1_P$1") (pintype "passive"))
      (node (ref "C50") (pin "P$1") (pinfunction "P$1_P$1") (pintype "passive"))
      (node (ref "C51") (pin "P$1") (pinfunction "P$1_P$1") (pintype "passive"))
      (node (ref "C52") (pin "P$1") (pinfunction "P$1_P$1") (pintype "passive"))
      (node (ref "C53") (pin "P$1") (pinfunction "P$1_P$1") (pintype "passive"))
      (node (ref "C54") (pin "P$1") (pinfunction "P$1_P$1") (pintype "passive"))
      (node (ref "J1") (pin "1") (pinfunction "1_1") (pintype "passive"))
      (node (ref "J2") (pin "1") (pinfunction "1_1") (pintype "passive"))
      (node (ref "Q1") (pin "5") (pinfunction "D_5") (pintype "passive"))
      (node (ref "Q1") (pin "6") (pinfunction "D_6") (pintype "passive"))
      (node (ref "Q1") (pin "7") (pinfunction "D_7") (pintype "passive"))
      (node (ref "Q1") (pin "8") (pinfunction "D_8") (pintype "passive"))
      (node (ref "Q1") (pin "PAD") (pinfunction "D_PAD") (pintype "passive"))
      (node (ref "Q3") (pin "5") (pinfunction "D_5") (pintype "passive"))
      (node (ref "Q3") (pin "6") (pinfunction "D_6") (pintype "passive"))
      (node (ref "Q3") (pin "7") (pinfunction "D_7") (pintype "passive"))
      (node (ref "Q3") (pin "8") (pinfunction "D_8") (pintype "passive"))
      (node (ref "Q3") (pin "PAD") (pinfunction "D_PAD") (pintype "passive"))
      (node (ref "Q5") (pin "5") (pinfunction "D_5") (pintype "passive"))
      (node (ref "Q5") (pin "6") (pinfunction "D_6") (pintype "passive"))
      (node (ref "Q5") (pin "7") (pinfunction "D_7") (pintype "passive"))
      (node (ref "Q5") (pin "8") (pinfunction "D_8") (pintype "passive"))
      (node (ref "Q5") (pin "PAD") (pinfunction "D_PAD") (pintype "passive"))
      (node (ref "R5") (pin "P$2") (pinfunction "P$2_P$2") (pintype "passive"))
      (node (ref "U4") (pin "1") (pinfunction "VIN_1") (pintype "input"))
      (node (ref "U4") (pin "2") (pinfunction "EN/UVLO_2") (pintype "input"))
      (node (ref "U5") (pin "3") (pinfunction "VM_3") (pintype "bidirectional"))
      (node (ref "U5") (pin "4") (pinfunction "VDRAIN_4") (pintype "bidirectional"))
    )
    (net (code "73") (name "V-") (class "Default")
      (node (ref "C14") (pin "P$2") (pinfunction "P$2_P$2") (pintype "passive"))
      (node (ref "C17") (pin "P$1") (pinfunction "P$1_P$1") (pintype "passive"))
      (node (ref "C19") (pin "P$2") (pinfunction "P$2_P$2") (pintype "passive"))
      (node (ref "C22") (pin "P$2") (pinfunction "P$2_P$2") (pintype "passive"))
      (node (ref "C23") (pin "P$2") (pinfunction "P$2_P$2") (pintype "passive"))
      (node (ref "C24") (pin "P$2") (pinfunction "P$2_P$2") (pintype "passive"))
      (node (ref "C25") (pin "P$2") (pinfunction "P$2_P$2") (pintype "passive"))
      (node (ref "C26") (pin "P$2") (pinfunction "P$2_P$2") (pintype "passive"))
      (node (ref "C27") (pin "P$2") (pinfunction "P$2_P$2") (pintype "passive"))
      (node (ref "C28") (pin "P$2") (pinfunction "P$2_P$2") (pintype "passive"))
      (node (ref "C29") (pin "P$2") (pinfunction "P$2_P$2") (pintype "passive"))
      (node (ref "C30") (pin "P$2") (pinfunction "P$2_P$2") (pintype "passive"))
      (node (ref "C31") (pin "P$2") (pinfunction "P$2_P$2") (pintype "passive"))
      (node (ref "C32") (pin "P$2") (pinfunction "P$2_P$2") (pintype "passive"))
      (node (ref "C33") (pin "P$2") (pinfunction "P$2_P$2") (pintype "passive"))
      (node (ref "C34") (pin "P$2") (pinfunction "P$2_P$2") (pintype "passive"))
      (node (ref "C35") (pin "P$2") (pinfunction "P$2_P$2") (pintype "passive"))
      (node (ref "C36") (pin "P$2") (pinfunction "P$2_P$2") (pintype "passive"))
      (node (ref "C37") (pin "P$2") (pinfunction "P$2_P$2") (pintype "passive"))
      (node (ref "C38") (pin "P$1") (pinfunction "P$1_P$1") (pintype "passive"))
      (node (ref "C39") (pin "P$2") (pinfunction "P$2_P$2") (pintype "passive"))
      (node (ref "C40") (pin "P$2") (pinfunction "P$2_P$2") (pintype "passive"))
      (node (ref "C41") (pin "P$2") (pinfunction "P$2_P$2") (pintype "passive"))
      (node (ref "C42") (pin "P$2") (pinfunction "P$2_P$2") (pintype "passive"))
      (node (ref "C43") (pin "P$2") (pinfunction "P$2_P$2") (pintype "passive"))
      (node (ref "C44") (pin "P$2") (pinfunction "P$2_P$2") (pintype "passive"))
      (node (ref "C45") (pin "P$2") (pinfunction "P$2_P$2") (pintype "passive"))
      (node (ref "C46") (pin "P$2") (pinfunction "P$2_P$2") (pintype "passive"))
      (node (ref "C47") (pin "P$2") (pinfunction "P$2_P$2") (pintype "passive"))
      (node (ref "C48") (pin "P$2") (pinfunction "P$2_P$2") (pintype "passive"))
      (node (ref "C49") (pin "P$2") (pinfunction "P$2_P$2") (pintype "passive"))
      (node (ref "C50") (pin "P$2") (pinfunction "P$2_P$2") (pintype "passive"))
      (node (ref "C51") (pin "P$2") (pinfunction "P$2_P$2") (pintype "passive"))
      (node (ref "C52") (pin "P$2") (pinfunction "P$2_P$2") (pintype "passive"))
      (node (ref "C53") (pin "P$2") (pinfunction "P$2_P$2") (pintype "passive"))
      (node (ref "C54") (pin "P$2") (pinfunction "P$2_P$2") (pintype "passive"))
      (node (ref "C55") (pin "P$2") (pinfunction "P$2_P$2") (pintype "passive"))
      (node (ref "J1") (pin "2") (pinfunction "2_2") (pintype "passive"))
      (node (ref "J2") (pin "2") (pinfunction "2_2") (pintype "passive"))
      (node (ref "R10") (pin "P$2") (pinfunction "P$2_P$2") (pintype "passive"))
      (node (ref "RA") (pin "1") (pinfunction "1_1") (pintype "passive"))
      (node (ref "RB") (pin "1") (pinfunction "1_1") (pintype "passive"))
      (node (ref "RC") (pin "1") (pinfunction "1_1") (pintype "passive"))
      (node (ref "SH1") (pin "2") (pinfunction "P$2_2") (pintype "bidirectional"))
      (node (ref "SH2") (pin "2") (pinfunction "P$2_2") (pintype "bidirectional"))
      (node (ref "SH3") (pin "2") (pinfunction "P$2_2") (pintype "bidirectional"))
      (node (ref "SH4") (pin "1") (pinfunction "P$1_1") (pintype "bidirectional"))
      (node (ref "U5") (pin "39") (pinfunction "GND_39") (pintype "bidirectional"))
      (node (ref "U5") (pin "P1") (pinfunction "PAD_P1") (pintype "bidirectional"))
      (node (ref "U5") (pin "P12") (pinfunction "PAD_P12") (pintype "bidirectional"))
      (node (ref "U5") (pin "P13") (pinfunction "PAD_P13") (pintype "bidirectional"))
      (node (ref "U5") (pin "P14") (pinfunction "PAD_P14") (pintype "bidirectional"))
      (node (ref "U5") (pin "P17") (pinfunction "PAD_P17") (pintype "bidirectional"))
      (node (ref "U5") (pin "P18") (pinfunction "PAD_P18") (pintype "bidirectional"))
      (node (ref "U5") (pin "P19") (pinfunction "PAD_P19") (pintype "bidirectional"))
      (node (ref "U5") (pin "P2") (pinfunction "PAD_P2") (pintype "bidirectional"))
      (node (ref "U5") (pin "P3") (pinfunction "PAD_P3") (pintype "bidirectional"))
      (node (ref "U5") (pin "P7") (pinfunction "PAD_P7") (pintype "bidirectional"))
      (node (ref "U5") (pin "P8") (pinfunction "PAD_P8") (pintype "bidirectional"))
      (node (ref "U5") (pin "P9") (pinfunction "PAD_P9") (pintype "bidirectional"))
      (node (ref "U5") (pin "PAD") (pinfunction "PAD_PAD") (pintype "bidirectional"))
    )
    (net (code "74") (name "unconnected-(M1-PadP$1)") (class "Default")
      (node (ref "M1") (pin "P$1") (pinfunction "P$1_P$1") (pintype "bidirectional"))
    )
    (net (code "75") (name "unconnected-(M2-PadP$1)") (class "Default")
      (node (ref "M2") (pin "P$1") (pinfunction "P$1_P$1") (pintype "bidirectional"))
    )
    (net (code "76") (name "unconnected-(M4-PadP$1)") (class "Default")
      (node (ref "M4") (pin "P$1") (pinfunction "P$1_P$1") (pintype "bidirectional"))
    )
    (net (code "77") (name "unconnected-(SWD-Pad1)") (class "Default")
      (node (ref "SWD") (pin "1") (pinfunction "1_1") (pintype "passive"))
    )
    (net (code "78") (name "unconnected-(U1-PA10-Pad32)") (class "Default")
      (node (ref "U1") (pin "32") (pinfunction "PA10_32") (pintype "bidirectional"))
    )
    (net (code "79") (name "unconnected-(U1-PB3-Pad41)") (class "Default")
      (node (ref "U1") (pin "41") (pinfunction "PB3_41") (pintype "bidirectional"))
    )
    (net (code "80") (name "unconnected-(U1-PB10-Pad22)") (class "Default")
      (node (ref "U1") (pin "22") (pinfunction "PB10_22") (pintype "bidirectional"))
    )
    (net (code "81") (name "unconnected-(U3-I-Pad14)") (class "Default")
      (node (ref "U3") (pin "14") (pinfunction "I_14") (pintype "bidirectional"))
    )
    (net (code "82") (name "unconnected-(U3-PWM-Pad8)") (class "Default")
      (node (ref "U3") (pin "8") (pinfunction "PWM_8") (pintype "bidirectional"))
    )
    (net (code "83") (name "unconnected-(U3-VDD5V-Pad11)") (class "Default")
      (node (ref "U3") (pin "11") (pinfunction "VDD5V_11") (pintype "bidirectional"))
    )
    (net (code "84") (name "unconnected-(U4-MODE-Pad5)") (class "Default")
      (node (ref "U4") (pin "5") (pinfunction "MODE_5") (pintype "input"))
    )
    (net (code "85") (name "unconnected-(U4-~{RESET}-Pad6)") (class "Default")
      (node (ref "U4") (pin "6") (pinfunction "~{RESET}_6") (pintype "output"))
    )
  )
)
